# vr61-revC.net
KiCad netlist of a schematic drawn in EAGLE
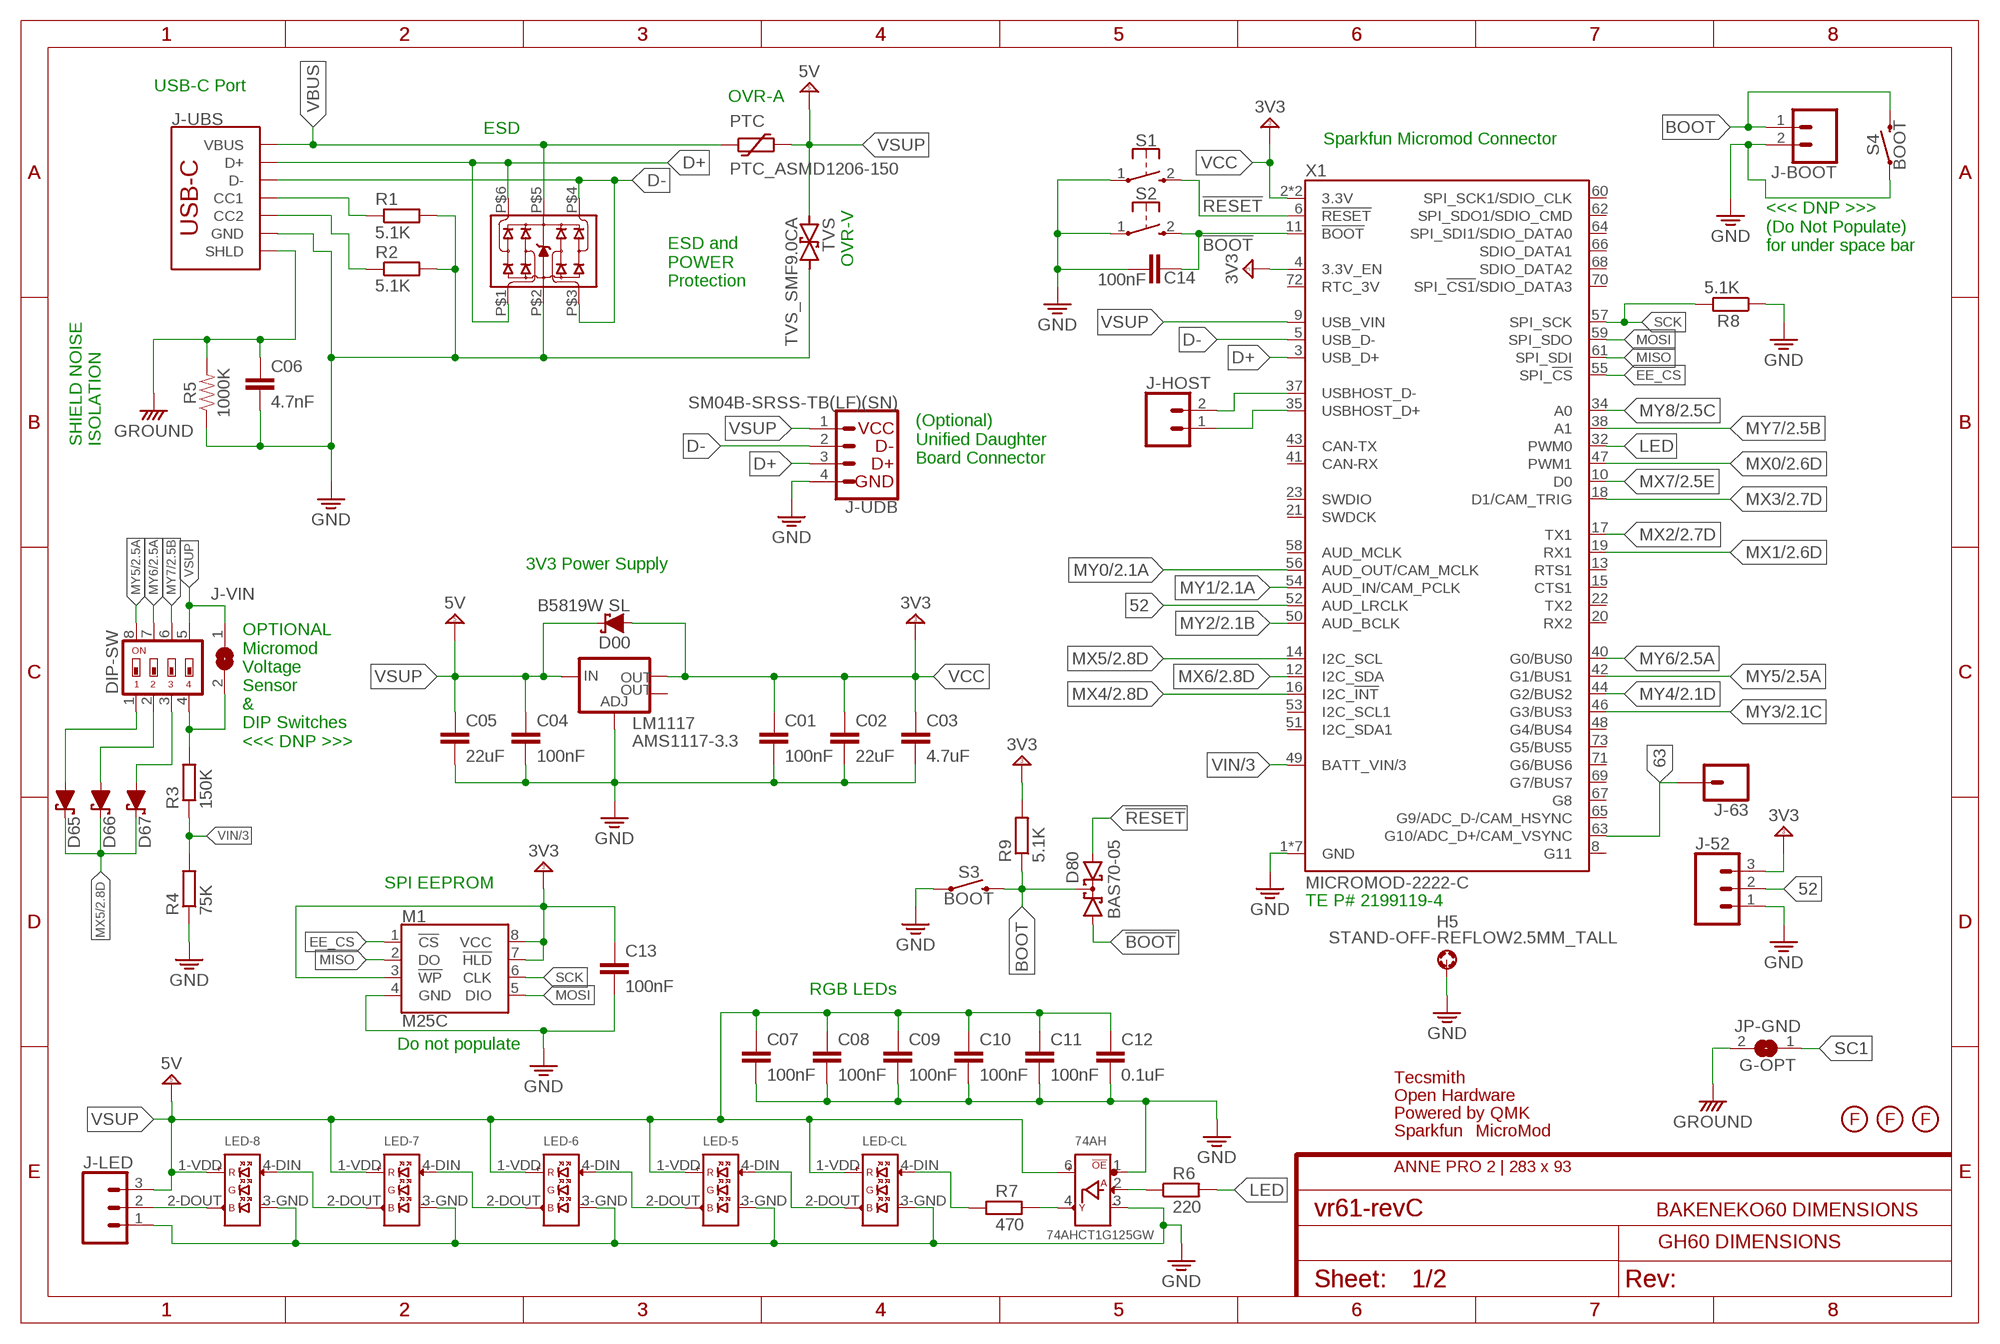
[diagram p0: schematic, sheet 1]
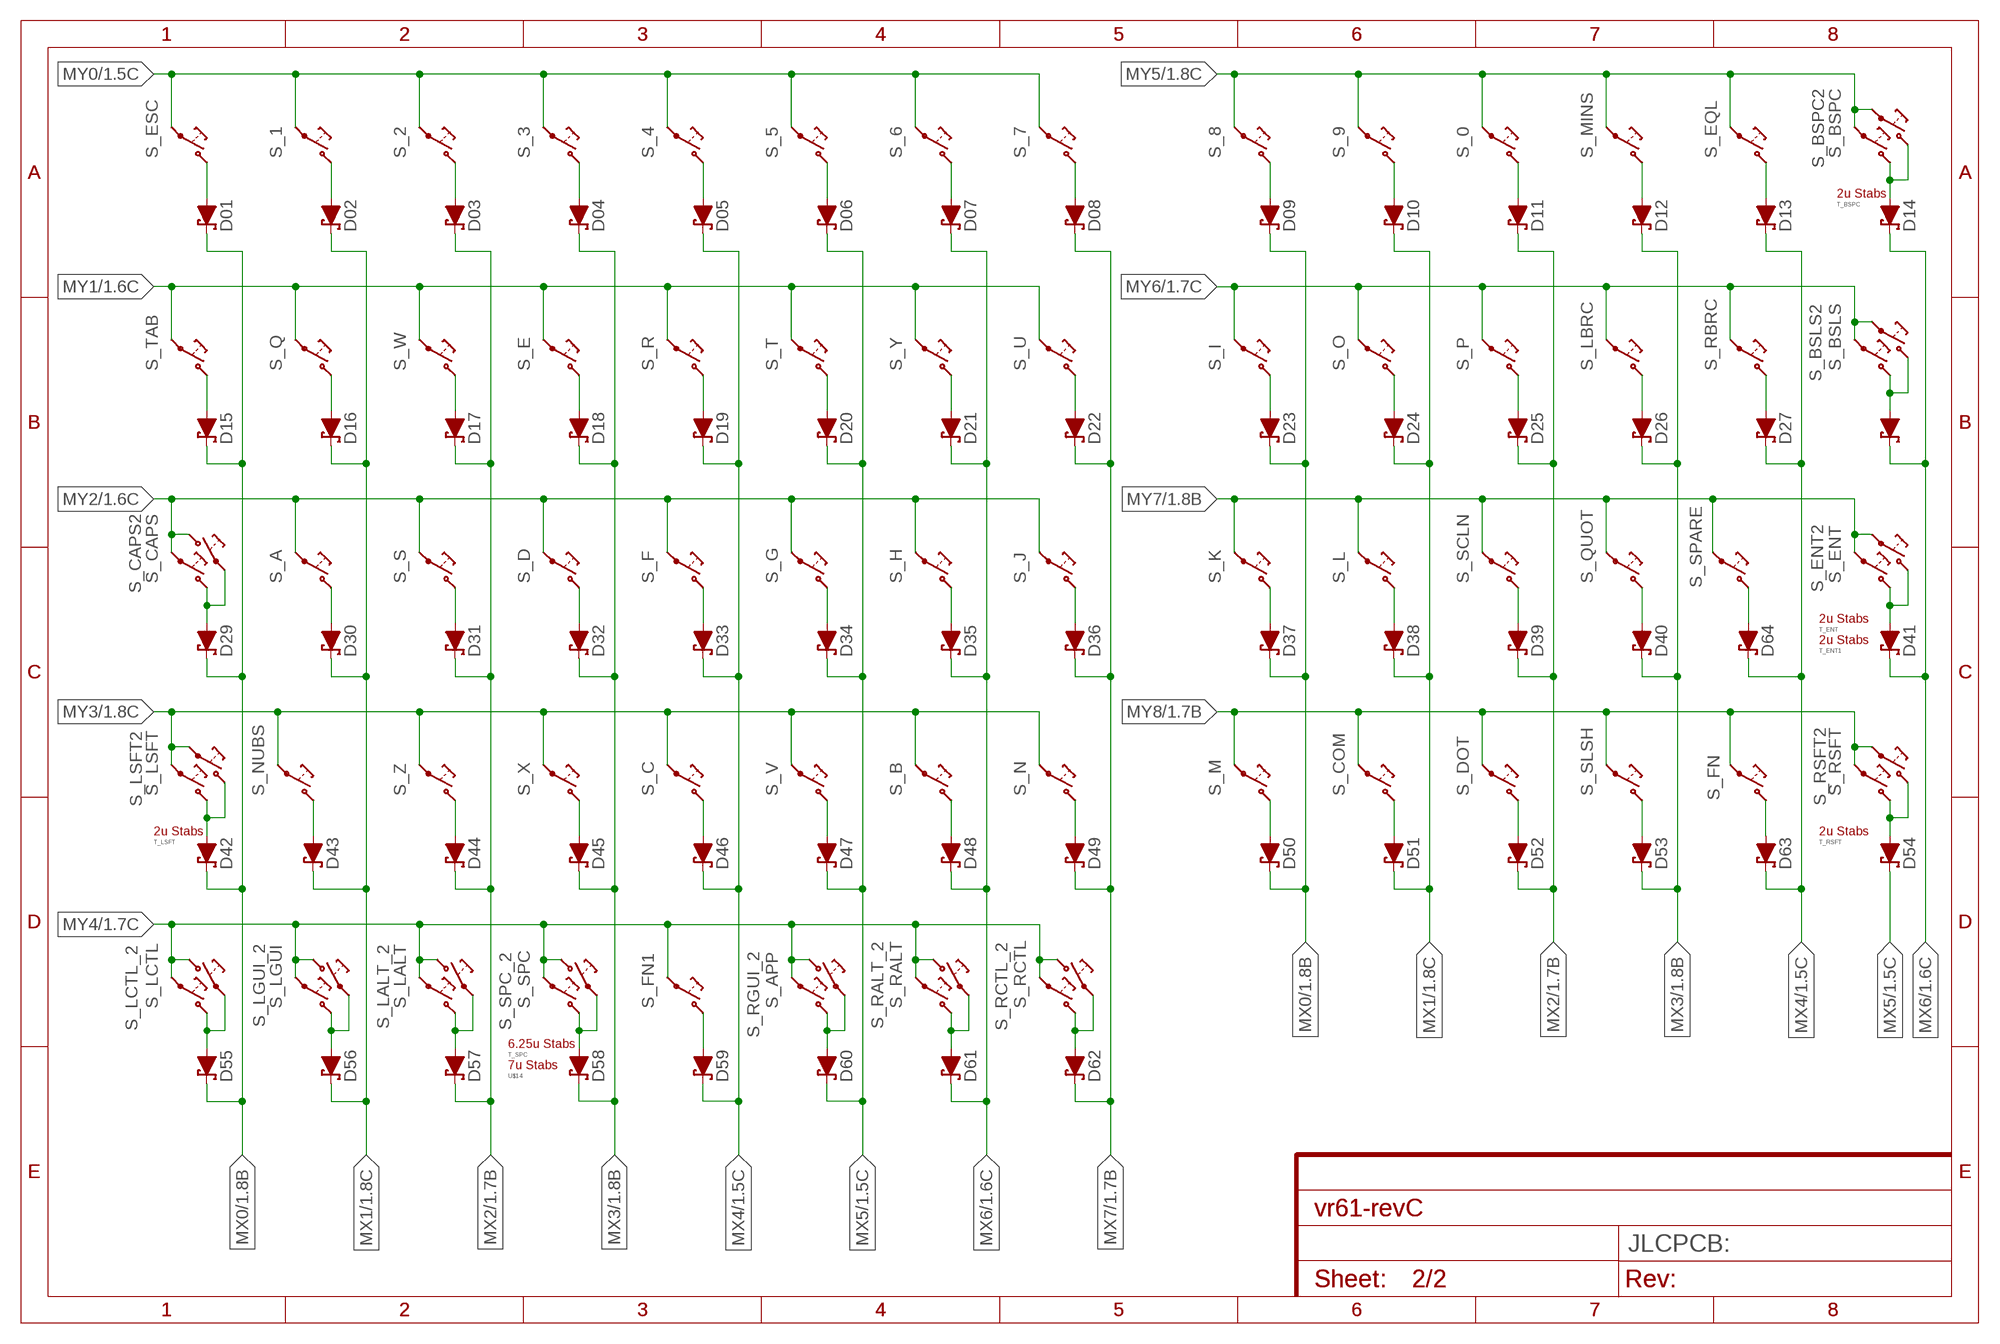
[diagram p1: schematic, sheet 2]

(export (version "E")
  (design (tool "Eeschema 10.0.6"))
  (components
    (comp (ref "D01")
      (value "1N5819WS")
      (footprint "eagle-import:SOD-123")
      (libsource (lib "eagle-import") (part "1N5819WS"))
    )
    (comp (ref "D02")
      (value "1N5819WS")
      (footprint "eagle-import:SOD-123")
      (libsource (lib "eagle-import") (part "1N5819WS"))
    )
    (comp (ref "D03")
      (value "1N5819WS")
      (footprint "eagle-import:SOD-123")
      (libsource (lib "eagle-import") (part "1N5819WS"))
    )
    (comp (ref "D04")
      (value "1N5819WS")
      (footprint "eagle-import:SOD-123")
      (libsource (lib "eagle-import") (part "1N5819WS"))
    )
    (comp (ref "D05")
      (value "1N5819WS")
      (footprint "eagle-import:SOD-123")
      (libsource (lib "eagle-import") (part "1N5819WS"))
    )
    (comp (ref "D06")
      (value "1N5819WS")
      (footprint "eagle-import:SOD-123")
      (libsource (lib "eagle-import") (part "1N5819WS"))
    )
    (comp (ref "D07")
      (value "1N5819WS")
      (footprint "eagle-import:SOD-123")
      (libsource (lib "eagle-import") (part "1N5819WS"))
    )
    (comp (ref "D08")
      (value "1N5819WS")
      (footprint "eagle-import:SOD-123")
      (libsource (lib "eagle-import") (part "1N5819WS"))
    )
    (comp (ref "D09")
      (value "1N5819WS")
      (footprint "eagle-import:SOD-123")
      (libsource (lib "eagle-import") (part "1N5819WS"))
    )
    (comp (ref "D10")
      (value "1N5819WS")
      (footprint "eagle-import:SOD-123")
      (libsource (lib "eagle-import") (part "1N5819WS"))
    )
    (comp (ref "D11")
      (value "1N5819WS")
      (footprint "eagle-import:SOD-123")
      (libsource (lib "eagle-import") (part "1N5819WS"))
    )
    (comp (ref "D12")
      (value "1N5819WS")
      (footprint "eagle-import:SOD-123")
      (libsource (lib "eagle-import") (part "1N5819WS"))
    )
    (comp (ref "D13")
      (value "1N5819WS")
      (footprint "eagle-import:SOD-123")
      (libsource (lib "eagle-import") (part "1N5819WS"))
    )
    (comp (ref "D14")
      (value "1N5819WS")
      (footprint "eagle-import:SOD-123")
      (libsource (lib "eagle-import") (part "1N5819WS"))
    )
    (comp (ref "D15")
      (value "1N5819WS")
      (footprint "eagle-import:SOD-123")
      (libsource (lib "eagle-import") (part "1N5819WS"))
    )
    (comp (ref "D16")
      (value "1N5819WS")
      (footprint "eagle-import:SOD-123")
      (libsource (lib "eagle-import") (part "1N5819WS"))
    )
    (comp (ref "D17")
      (value "1N5819WS")
      (footprint "eagle-import:SOD-123")
      (libsource (lib "eagle-import") (part "1N5819WS"))
    )
    (comp (ref "D18")
      (value "1N5819WS")
      (footprint "eagle-import:SOD-123")
      (libsource (lib "eagle-import") (part "1N5819WS"))
    )
    (comp (ref "D19")
      (value "1N5819WS")
      (footprint "eagle-import:SOD-123")
      (libsource (lib "eagle-import") (part "1N5819WS"))
    )
    (comp (ref "D20")
      (value "1N5819WS")
      (footprint "eagle-import:SOD-123")
      (libsource (lib "eagle-import") (part "1N5819WS"))
    )
    (comp (ref "D21")
      (value "1N5819WS")
      (footprint "eagle-import:SOD-123")
      (libsource (lib "eagle-import") (part "1N5819WS"))
    )
    (comp (ref "D22")
      (value "1N5819WS")
      (footprint "eagle-import:SOD-123")
      (libsource (lib "eagle-import") (part "1N5819WS"))
    )
    (comp (ref "D23")
      (value "1N5819WS")
      (footprint "eagle-import:SOD-123")
      (libsource (lib "eagle-import") (part "1N5819WS"))
    )
    (comp (ref "D24")
      (value "1N5819WS")
      (footprint "eagle-import:SOD-123")
      (libsource (lib "eagle-import") (part "1N5819WS"))
    )
    (comp (ref "D25")
      (value "1N5819WS")
      (footprint "eagle-import:SOD-123")
      (libsource (lib "eagle-import") (part "1N5819WS"))
    )
    (comp (ref "D26")
      (value "1N5819WS")
      (footprint "eagle-import:SOD-123")
      (libsource (lib "eagle-import") (part "1N5819WS"))
    )
    (comp (ref "D27")
      (value "1N5819WS")
      (footprint "eagle-import:SOD-123")
      (libsource (lib "eagle-import") (part "1N5819WS"))
    )
    (comp (ref "D28")
      (value "1N5819WS")
      (footprint "eagle-import:SOD-123")
      (libsource (lib "eagle-import") (part "1N5819WS"))
    )
    (comp (ref "D29")
      (value "1N5819WS")
      (footprint "eagle-import:SOD-123")
      (libsource (lib "eagle-import") (part "1N5819WS"))
    )
    (comp (ref "D30")
      (value "1N5819WS")
      (footprint "eagle-import:SOD-123")
      (libsource (lib "eagle-import") (part "1N5819WS"))
    )
    (comp (ref "D31")
      (value "1N5819WS")
      (footprint "eagle-import:SOD-123")
      (libsource (lib "eagle-import") (part "1N5819WS"))
    )
    (comp (ref "D32")
      (value "1N5819WS")
      (footprint "eagle-import:SOD-123")
      (libsource (lib "eagle-import") (part "1N5819WS"))
    )
    (comp (ref "D33")
      (value "1N5819WS")
      (footprint "eagle-import:SOD-123")
      (libsource (lib "eagle-import") (part "1N5819WS"))
    )
    (comp (ref "D34")
      (value "1N5819WS")
      (footprint "eagle-import:SOD-123")
      (libsource (lib "eagle-import") (part "1N5819WS"))
    )
    (comp (ref "D35")
      (value "1N5819WS")
      (footprint "eagle-import:SOD-123")
      (libsource (lib "eagle-import") (part "1N5819WS"))
    )
    (comp (ref "D36")
      (value "1N5819WS")
      (footprint "eagle-import:SOD-123")
      (libsource (lib "eagle-import") (part "1N5819WS"))
    )
    (comp (ref "D37")
      (value "1N5819WS")
      (footprint "eagle-import:SOD-123")
      (libsource (lib "eagle-import") (part "1N5819WS"))
    )
    (comp (ref "D38")
      (value "1N5819WS")
      (footprint "eagle-import:SOD-123")
      (libsource (lib "eagle-import") (part "1N5819WS"))
    )
    (comp (ref "D39")
      (value "1N5819WS")
      (footprint "eagle-import:SOD-123")
      (libsource (lib "eagle-import") (part "1N5819WS"))
    )
    (comp (ref "D40")
      (value "1N5819WS")
      (footprint "eagle-import:SOD-123")
      (libsource (lib "eagle-import") (part "1N5819WS"))
    )
    (comp (ref "D41")
      (value "1N5819WS")
      (footprint "eagle-import:SOD-123")
      (libsource (lib "eagle-import") (part "1N5819WS"))
    )
    (comp (ref "D42")
      (value "1N5819WS")
      (footprint "eagle-import:SOD-123")
      (libsource (lib "eagle-import") (part "1N5819WS"))
    )
    (comp (ref "D43")
      (value "1N5819WS")
      (footprint "eagle-import:SOD-123")
      (libsource (lib "eagle-import") (part "1N5819WS"))
    )
    (comp (ref "D44")
      (value "1N5819WS")
      (footprint "eagle-import:SOD-123")
      (libsource (lib "eagle-import") (part "1N5819WS"))
    )
    (comp (ref "D45")
      (value "1N5819WS")
      (footprint "eagle-import:SOD-123")
      (libsource (lib "eagle-import") (part "1N5819WS"))
    )
    (comp (ref "D46")
      (value "1N5819WS")
      (footprint "eagle-import:SOD-123")
      (libsource (lib "eagle-import") (part "1N5819WS"))
    )
    (comp (ref "D47")
      (value "1N5819WS")
      (footprint "eagle-import:SOD-123")
      (libsource (lib "eagle-import") (part "1N5819WS"))
    )
    (comp (ref "D48")
      (value "1N5819WS")
      (footprint "eagle-import:SOD-123")
      (libsource (lib "eagle-import") (part "1N5819WS"))
    )
    (comp (ref "D49")
      (value "1N5819WS")
      (footprint "eagle-import:SOD-123")
      (libsource (lib "eagle-import") (part "1N5819WS"))
    )
    (comp (ref "D50")
      (value "1N5819WS")
      (footprint "eagle-import:SOD-123")
      (libsource (lib "eagle-import") (part "1N5819WS"))
    )
    (comp (ref "D51")
      (value "1N5819WS")
      (footprint "eagle-import:SOD-123")
      (libsource (lib "eagle-import") (part "1N5819WS"))
    )
    (comp (ref "D52")
      (value "1N5819WS")
      (footprint "eagle-import:SOD-123")
      (libsource (lib "eagle-import") (part "1N5819WS"))
    )
    (comp (ref "D53")
      (value "1N5819WS")
      (footprint "eagle-import:SOD-123")
      (libsource (lib "eagle-import") (part "1N5819WS"))
    )
    (comp (ref "D54")
      (value "1N5819WS")
      (footprint "eagle-import:SOD-123")
      (libsource (lib "eagle-import") (part "1N5819WS"))
    )
    (comp (ref "D55")
      (value "1N5819WS")
      (footprint "eagle-import:SOD-123")
      (libsource (lib "eagle-import") (part "1N5819WS"))
    )
    (comp (ref "D56")
      (value "1N5819WS")
      (footprint "eagle-import:SOD-123")
      (libsource (lib "eagle-import") (part "1N5819WS"))
    )
    (comp (ref "D57")
      (value "1N5819WS")
      (footprint "eagle-import:SOD-123")
      (libsource (lib "eagle-import") (part "1N5819WS"))
    )
    (comp (ref "D58")
      (value "1N5819WS")
      (footprint "eagle-import:SOD-123")
      (libsource (lib "eagle-import") (part "1N5819WS"))
    )
    (comp (ref "D59")
      (value "1N5819WS")
      (footprint "eagle-import:SOD-123")
      (libsource (lib "eagle-import") (part "1N5819WS"))
    )
    (comp (ref "D60")
      (value "1N5819WS")
      (footprint "eagle-import:SOD-123")
      (libsource (lib "eagle-import") (part "1N5819WS"))
    )
    (comp (ref "D61")
      (value "1N5819WS")
      (footprint "eagle-import:SOD-123")
      (libsource (lib "eagle-import") (part "1N5819WS"))
    )
    (comp (ref "D62")
      (value "1N5819WS")
      (footprint "eagle-import:SOD-123")
      (libsource (lib "eagle-import") (part "1N5819WS"))
    )
    (comp (ref "D63")
      (value "1N5819WS")
      (footprint "eagle-import:SOD-123")
      (libsource (lib "eagle-import") (part "1N5819WS"))
    )
    (comp (ref "D64")
      (value "1N5819WS")
      (footprint "eagle-import:SOD-123")
      (libsource (lib "eagle-import") (part "1N5819WS"))
    )
    (comp (ref "S_0")
      (value "MX-5-PIN-HOTSWAP-VIA")
      (footprint "eagle-import:MX-5-PIN-HOTSWAP-VIA")
      (libsource (lib "eagle-import") (part "MX-5-PIN-HOTSWAP-VIA"))
    )
    (comp (ref "S_1")
      (value "MX-5-PIN-HOTSWAP-VIA")
      (footprint "eagle-import:MX-5-PIN-HOTSWAP-VIA")
      (libsource (lib "eagle-import") (part "MX-5-PIN-HOTSWAP-VIA"))
    )
    (comp (ref "S_2")
      (value "MX-5-PIN-HOTSWAP-VIA")
      (footprint "eagle-import:MX-5-PIN-HOTSWAP-VIA")
      (libsource (lib "eagle-import") (part "MX-5-PIN-HOTSWAP-VIA"))
    )
    (comp (ref "S_3")
      (value "MX-5-PIN-HOTSWAP-VIA")
      (footprint "eagle-import:MX-5-PIN-HOTSWAP-VIA")
      (libsource (lib "eagle-import") (part "MX-5-PIN-HOTSWAP-VIA"))
    )
    (comp (ref "S_4")
      (value "MX-5-PIN-HOTSWAP-VIA")
      (footprint "eagle-import:MX-5-PIN-HOTSWAP-VIA")
      (libsource (lib "eagle-import") (part "MX-5-PIN-HOTSWAP-VIA"))
    )
    (comp (ref "S_5")
      (value "MX-5-PIN-HOTSWAP-VIA")
      (footprint "eagle-import:MX-5-PIN-HOTSWAP-VIA")
      (libsource (lib "eagle-import") (part "MX-5-PIN-HOTSWAP-VIA"))
    )
    (comp (ref "S_6")
      (value "MX-5-PIN-HOTSWAP-VIA")
      (footprint "eagle-import:MX-5-PIN-HOTSWAP-VIA")
      (libsource (lib "eagle-import") (part "MX-5-PIN-HOTSWAP-VIA"))
    )
    (comp (ref "S_7")
      (value "MX-5-PIN-HOTSWAP-VIA")
      (footprint "eagle-import:MX-5-PIN-HOTSWAP-VIA")
      (libsource (lib "eagle-import") (part "MX-5-PIN-HOTSWAP-VIA"))
    )
    (comp (ref "S_8")
      (value "MX-5-PIN-HOTSWAP-VIA")
      (footprint "eagle-import:MX-5-PIN-HOTSWAP-VIA")
      (libsource (lib "eagle-import") (part "MX-5-PIN-HOTSWAP-VIA"))
    )
    (comp (ref "S_9")
      (value "MX-5-PIN-HOTSWAP-VIA")
      (footprint "eagle-import:MX-5-PIN-HOTSWAP-VIA")
      (libsource (lib "eagle-import") (part "MX-5-PIN-HOTSWAP-VIA"))
    )
    (comp (ref "S_A")
      (value "MX-5-PIN-HOTSWAP-VIA")
      (footprint "eagle-import:MX-5-PIN-HOTSWAP-VIA")
      (libsource (lib "eagle-import") (part "MX-5-PIN-HOTSWAP-VIA"))
    )
    (comp (ref "S_APP")
      (value "MX-5-PIN-HOTSWAP-VIA")
      (footprint "eagle-import:MX-5-PIN-HOTSWAP-VIA")
      (libsource (lib "eagle-import") (part "MX-5-PIN-HOTSWAP-VIA"))
    )
    (comp (ref "S_B")
      (value "MX-5-PIN-HOTSWAP-VIA")
      (footprint "eagle-import:MX-5-PIN-HOTSWAP-VIA")
      (libsource (lib "eagle-import") (part "MX-5-PIN-HOTSWAP-VIA"))
    )
    (comp (ref "S_BSLS")
      (value "MX-5-PIN-HOTSWAP-VIA")
      (footprint "eagle-import:MX-5-PIN-HOTSWAP-VIA")
      (libsource (lib "eagle-import") (part "MX-5-PIN-HOTSWAP-VIA"))
    )
    (comp (ref "S_BSLS2")
      (value "MX-5-PIN-HOTSWAP-VIANO-SILK")
      (footprint "eagle-import:MX-5-PIN-HOTSWAP-VIA-NS")
      (libsource (lib "eagle-import") (part "MX-5-PIN-HOTSWAP-VIANO-SILK"))
    )
    (comp (ref "S_BSPC")
      (value "MX-5-PIN-HOTSWAP-VIA")
      (footprint "eagle-import:MX-5-PIN-HOTSWAP-VIA")
      (libsource (lib "eagle-import") (part "MX-5-PIN-HOTSWAP-VIA"))
    )
    (comp (ref "S_BSPC2")
      (value "MX-5-PIN-HOTSWAP-VIANO-SILK")
      (footprint "eagle-import:MX-5-PIN-HOTSWAP-VIA-NS")
      (libsource (lib "eagle-import") (part "MX-5-PIN-HOTSWAP-VIANO-SILK"))
    )
    (comp (ref "S_C")
      (value "MX-5-PIN-HOTSWAP-VIA")
      (footprint "eagle-import:MX-5-PIN-HOTSWAP-VIA")
      (libsource (lib "eagle-import") (part "MX-5-PIN-HOTSWAP-VIA"))
    )
    (comp (ref "S_CAPS")
      (value "MX-5-PIN-HOTSWAP-VIA")
      (footprint "eagle-import:MX-5-PIN-HOTSWAP-VIA")
      (libsource (lib "eagle-import") (part "MX-5-PIN-HOTSWAP-VIA"))
    )
    (comp (ref "S_CAPS2")
      (value "MX-5-PIN-MILMAX-3305-XNO-SILK")
      (footprint "eagle-import:MX-5-PIN-MILMAX-3305-X-NS")
      (libsource (lib "eagle-import") (part "MX-5-PIN-MILMAX-3305-XNO-SILK"))
    )
    (comp (ref "S_COM")
      (value "MX-5-PIN-HOTSWAP-VIA")
      (footprint "eagle-import:MX-5-PIN-HOTSWAP-VIA")
      (libsource (lib "eagle-import") (part "MX-5-PIN-HOTSWAP-VIA"))
    )
    (comp (ref "S_D")
      (value "MX-5-PIN-HOTSWAP-VIA")
      (footprint "eagle-import:MX-5-PIN-HOTSWAP-VIA")
      (libsource (lib "eagle-import") (part "MX-5-PIN-HOTSWAP-VIA"))
    )
    (comp (ref "S_DOT")
      (value "MX-5-PIN-HOTSWAP-VIA")
      (footprint "eagle-import:MX-5-PIN-HOTSWAP-VIA")
      (libsource (lib "eagle-import") (part "MX-5-PIN-HOTSWAP-VIA"))
    )
    (comp (ref "S_E")
      (value "MX-5-PIN-HOTSWAP-VIA")
      (footprint "eagle-import:MX-5-PIN-HOTSWAP-VIA")
      (libsource (lib "eagle-import") (part "MX-5-PIN-HOTSWAP-VIA"))
    )
    (comp (ref "S_ENT")
      (value "MX-5-PIN-HOTSWAP-VIA")
      (footprint "eagle-import:MX-5-PIN-HOTSWAP-VIA")
      (libsource (lib "eagle-import") (part "MX-5-PIN-HOTSWAP-VIA"))
    )
    (comp (ref "S_ENT2")
      (value "MX-5-PIN-HOTSWAP-VIANO-SILK")
      (footprint "eagle-import:MX-5-PIN-HOTSWAP-VIA-NS")
      (libsource (lib "eagle-import") (part "MX-5-PIN-HOTSWAP-VIANO-SILK"))
    )
    (comp (ref "S_EQL")
      (value "MX-5-PIN-HOTSWAP-VIA")
      (footprint "eagle-import:MX-5-PIN-HOTSWAP-VIA")
      (libsource (lib "eagle-import") (part "MX-5-PIN-HOTSWAP-VIA"))
    )
    (comp (ref "S_ESC")
      (value "MX-5-PIN-HOTSWAP-VIA")
      (footprint "eagle-import:MX-5-PIN-HOTSWAP-VIA")
      (libsource (lib "eagle-import") (part "MX-5-PIN-HOTSWAP-VIA"))
    )
    (comp (ref "S_F")
      (value "MX-5-PIN-HOTSWAP-VIA")
      (footprint "eagle-import:MX-5-PIN-HOTSWAP-VIA")
      (libsource (lib "eagle-import") (part "MX-5-PIN-HOTSWAP-VIA"))
    )
    (comp (ref "S_FN")
      (value "MX-5-PIN-HOTSWAP-VIANO-SILK")
      (footprint "eagle-import:MX-5-PIN-HOTSWAP-VIA-NS")
      (libsource (lib "eagle-import") (part "MX-5-PIN-HOTSWAP-VIANO-SILK"))
    )
    (comp (ref "S_FN1")
      (value "MX-5-PIN-HOTSWAP-VIA")
      (footprint "eagle-import:MX-5-PIN-HOTSWAP-VIA")
      (libsource (lib "eagle-import") (part "MX-5-PIN-HOTSWAP-VIA"))
    )
    (comp (ref "S_G")
      (value "MX-5-PIN-HOTSWAP-VIA")
      (footprint "eagle-import:MX-5-PIN-HOTSWAP-VIA")
      (libsource (lib "eagle-import") (part "MX-5-PIN-HOTSWAP-VIA"))
    )
    (comp (ref "S_H")
      (value "MX-5-PIN-HOTSWAP-VIA")
      (footprint "eagle-import:MX-5-PIN-HOTSWAP-VIA")
      (libsource (lib "eagle-import") (part "MX-5-PIN-HOTSWAP-VIA"))
    )
    (comp (ref "S_I")
      (value "MX-5-PIN-HOTSWAP-VIA")
      (footprint "eagle-import:MX-5-PIN-HOTSWAP-VIA")
      (libsource (lib "eagle-import") (part "MX-5-PIN-HOTSWAP-VIA"))
    )
    (comp (ref "S_J")
      (value "MX-5-PIN-HOTSWAP-VIA")
      (footprint "eagle-import:MX-5-PIN-HOTSWAP-VIA")
      (libsource (lib "eagle-import") (part "MX-5-PIN-HOTSWAP-VIA"))
    )
    (comp (ref "S_K")
      (value "MX-5-PIN-HOTSWAP-VIA")
      (footprint "eagle-import:MX-5-PIN-HOTSWAP-VIA")
      (libsource (lib "eagle-import") (part "MX-5-PIN-HOTSWAP-VIA"))
    )
    (comp (ref "S_L")
      (value "MX-5-PIN-HOTSWAP-VIA")
      (footprint "eagle-import:MX-5-PIN-HOTSWAP-VIA")
      (libsource (lib "eagle-import") (part "MX-5-PIN-HOTSWAP-VIA"))
    )
    (comp (ref "S_LALT")
      (value "MX-5-PIN-HOTSWAP-VIA")
      (footprint "eagle-import:MX-5-PIN-HOTSWAP-VIA")
      (libsource (lib "eagle-import") (part "MX-5-PIN-HOTSWAP-VIA"))
    )
    (comp (ref "S_LALT_2")
      (value "MX-5-PIN-HOTSWAP-VIANO-SILK")
      (footprint "eagle-import:MX-5-PIN-HOTSWAP-VIA-NS")
      (libsource (lib "eagle-import") (part "MX-5-PIN-HOTSWAP-VIANO-SILK"))
    )
    (comp (ref "S_LBRC")
      (value "MX-5-PIN-HOTSWAP-VIA")
      (footprint "eagle-import:MX-5-PIN-HOTSWAP-VIA")
      (libsource (lib "eagle-import") (part "MX-5-PIN-HOTSWAP-VIA"))
    )
    (comp (ref "S_LCTL")
      (value "MX-5-PIN-HOTSWAP-VIA")
      (footprint "eagle-import:MX-5-PIN-HOTSWAP-VIA")
      (libsource (lib "eagle-import") (part "MX-5-PIN-HOTSWAP-VIA"))
    )
    (comp (ref "S_LCTL_2")
      (value "MX-5-PIN-HOTSWAP-VIANO-SILK")
      (footprint "eagle-import:MX-5-PIN-HOTSWAP-VIA-NS")
      (libsource (lib "eagle-import") (part "MX-5-PIN-HOTSWAP-VIANO-SILK"))
    )
    (comp (ref "S_LGUI")
      (value "MX-5-PIN-HOTSWAP-VIA")
      (footprint "eagle-import:MX-5-PIN-HOTSWAP-VIA")
      (libsource (lib "eagle-import") (part "MX-5-PIN-HOTSWAP-VIA"))
    )
    (comp (ref "S_LGUI_2")
      (value "MX-5-PIN-HOTSWAP-VIANO-SILK")
      (footprint "eagle-import:MX-5-PIN-HOTSWAP-VIA-NS")
      (libsource (lib "eagle-import") (part "MX-5-PIN-HOTSWAP-VIANO-SILK"))
    )
    (comp (ref "S_LSFT")
      (value "MX-5-PIN-HOTSWAP-VIA")
      (footprint "eagle-import:MX-5-PIN-HOTSWAP-VIA")
      (libsource (lib "eagle-import") (part "MX-5-PIN-HOTSWAP-VIA"))
    )
    (comp (ref "S_LSFT2")
      (value "MX-5-PIN-HOTSWAP-VIANO-SILK")
      (footprint "eagle-import:MX-5-PIN-HOTSWAP-VIA-NS")
      (libsource (lib "eagle-import") (part "MX-5-PIN-HOTSWAP-VIANO-SILK"))
    )
    (comp (ref "S_M")
      (value "MX-5-PIN-HOTSWAP-VIA")
      (footprint "eagle-import:MX-5-PIN-HOTSWAP-VIA")
      (libsource (lib "eagle-import") (part "MX-5-PIN-HOTSWAP-VIA"))
    )
    (comp (ref "S_MINS")
      (value "MX-5-PIN-HOTSWAP-VIA")
      (footprint "eagle-import:MX-5-PIN-HOTSWAP-VIA")
      (libsource (lib "eagle-import") (part "MX-5-PIN-HOTSWAP-VIA"))
    )
    (comp (ref "S_N")
      (value "MX-5-PIN-HOTSWAP-VIA")
      (footprint "eagle-import:MX-5-PIN-HOTSWAP-VIA")
      (libsource (lib "eagle-import") (part "MX-5-PIN-HOTSWAP-VIA"))
    )
    (comp (ref "S_NUBS")
      (value "MX-5-PIN-HOTSWAP-VIANO-SILK")
      (footprint "eagle-import:MX-5-PIN-HOTSWAP-VIA-NS")
      (libsource (lib "eagle-import") (part "MX-5-PIN-HOTSWAP-VIANO-SILK"))
    )
    (comp (ref "S_O")
      (value "MX-5-PIN-HOTSWAP-VIA")
      (footprint "eagle-import:MX-5-PIN-HOTSWAP-VIA")
      (libsource (lib "eagle-import") (part "MX-5-PIN-HOTSWAP-VIA"))
    )
    (comp (ref "S_P")
      (value "MX-5-PIN-HOTSWAP-VIA")
      (footprint "eagle-import:MX-5-PIN-HOTSWAP-VIA")
      (libsource (lib "eagle-import") (part "MX-5-PIN-HOTSWAP-VIA"))
    )
    (comp (ref "S_Q")
      (value "MX-5-PIN-HOTSWAP-VIA")
      (footprint "eagle-import:MX-5-PIN-HOTSWAP-VIA")
      (libsource (lib "eagle-import") (part "MX-5-PIN-HOTSWAP-VIA"))
    )
    (comp (ref "S_QUOT")
      (value "MX-5-PIN-HOTSWAP-VIA")
      (footprint "eagle-import:MX-5-PIN-HOTSWAP-VIA")
      (libsource (lib "eagle-import") (part "MX-5-PIN-HOTSWAP-VIA"))
    )
    (comp (ref "S_R")
      (value "MX-5-PIN-HOTSWAP-VIA")
      (footprint "eagle-import:MX-5-PIN-HOTSWAP-VIA")
      (libsource (lib "eagle-import") (part "MX-5-PIN-HOTSWAP-VIA"))
    )
    (comp (ref "S_RALT")
      (value "MX-5-PIN-HOTSWAP-VIA")
      (footprint "eagle-import:MX-5-PIN-HOTSWAP-VIA")
      (libsource (lib "eagle-import") (part "MX-5-PIN-HOTSWAP-VIA"))
    )
    (comp (ref "S_RALT_2")
      (value "MX-5-PIN-HOTSWAP-VIANO-SILK")
      (footprint "eagle-import:MX-5-PIN-HOTSWAP-VIA-NS")
      (libsource (lib "eagle-import") (part "MX-5-PIN-HOTSWAP-VIANO-SILK"))
    )
    (comp (ref "S_RBRC")
      (value "MX-5-PIN-HOTSWAP-VIA")
      (footprint "eagle-import:MX-5-PIN-HOTSWAP-VIA")
      (libsource (lib "eagle-import") (part "MX-5-PIN-HOTSWAP-VIA"))
    )
    (comp (ref "S_RCTL")
      (value "MX-5-PIN-HOTSWAP-VIA")
      (footprint "eagle-import:MX-5-PIN-HOTSWAP-VIA")
      (libsource (lib "eagle-import") (part "MX-5-PIN-HOTSWAP-VIA"))
    )
    (comp (ref "S_RCTL_2")
      (value "MX-5-PIN-HOTSWAP-VIANO-SILK")
      (footprint "eagle-import:MX-5-PIN-HOTSWAP-VIA-NS")
      (libsource (lib "eagle-import") (part "MX-5-PIN-HOTSWAP-VIANO-SILK"))
    )
    (comp (ref "S_RGUI_2")
      (value "MX-5-PIN-HOTSWAP-VIANO-SILK")
      (footprint "eagle-import:MX-5-PIN-HOTSWAP-VIA-NS")
      (libsource (lib "eagle-import") (part "MX-5-PIN-HOTSWAP-VIANO-SILK"))
    )
    (comp (ref "S_RSFT")
      (value "MX-5-PIN-HOTSWAP-VIA")
      (footprint "eagle-import:MX-5-PIN-HOTSWAP-VIA")
      (libsource (lib "eagle-import") (part "MX-5-PIN-HOTSWAP-VIA"))
    )
    (comp (ref "S_RSFT2")
      (value "MX-5-PIN-HOTSWAP-VIANO-SILK")
      (footprint "eagle-import:MX-5-PIN-HOTSWAP-VIA-NS")
      (libsource (lib "eagle-import") (part "MX-5-PIN-HOTSWAP-VIANO-SILK"))
    )
    (comp (ref "S_S")
      (value "MX-5-PIN-HOTSWAP-VIA")
      (footprint "eagle-import:MX-5-PIN-HOTSWAP-VIA")
      (libsource (lib "eagle-import") (part "MX-5-PIN-HOTSWAP-VIA"))
    )
    (comp (ref "S_SCLN")
      (value "MX-5-PIN-HOTSWAP-VIA")
      (footprint "eagle-import:MX-5-PIN-HOTSWAP-VIA")
      (libsource (lib "eagle-import") (part "MX-5-PIN-HOTSWAP-VIA"))
    )
    (comp (ref "S_SLSH")
      (value "MX-5-PIN-HOTSWAP-VIA")
      (footprint "eagle-import:MX-5-PIN-HOTSWAP-VIA")
      (libsource (lib "eagle-import") (part "MX-5-PIN-HOTSWAP-VIA"))
    )
    (comp (ref "S_SPARE")
      (value "MX-5-PIN-HOTSWAP-VIANO-SILK")
      (footprint "eagle-import:MX-5-PIN-HOTSWAP-VIA-NS")
      (libsource (lib "eagle-import") (part "MX-5-PIN-HOTSWAP-VIANO-SILK"))
    )
    (comp (ref "S_SPC")
      (value "MX-5-PIN-HOTSWAP-VIA")
      (footprint "eagle-import:MX-5-PIN-HOTSWAP-VIA")
      (libsource (lib "eagle-import") (part "MX-5-PIN-HOTSWAP-VIA"))
    )
    (comp (ref "S_SPC_2")
      (value "MX-5-PIN-HOTSWAP-VIANO-SILK")
      (footprint "eagle-import:MX-5-PIN-HOTSWAP-VIA-NS")
      (libsource (lib "eagle-import") (part "MX-5-PIN-HOTSWAP-VIANO-SILK"))
    )
    (comp (ref "S_T")
      (value "MX-5-PIN-HOTSWAP-VIA")
      (footprint "eagle-import:MX-5-PIN-HOTSWAP-VIA")
      (libsource (lib "eagle-import") (part "MX-5-PIN-HOTSWAP-VIA"))
    )
    (comp (ref "S_TAB")
      (value "MX-5-PIN-HOTSWAP-VIA")
      (footprint "eagle-import:MX-5-PIN-HOTSWAP-VIA")
      (libsource (lib "eagle-import") (part "MX-5-PIN-HOTSWAP-VIA"))
    )
    (comp (ref "S_U")
      (value "MX-5-PIN-HOTSWAP-VIA")
      (footprint "eagle-import:MX-5-PIN-HOTSWAP-VIA")
      (libsource (lib "eagle-import") (part "MX-5-PIN-HOTSWAP-VIA"))
    )
    (comp (ref "S_V")
      (value "MX-5-PIN-HOTSWAP-VIA")
      (footprint "eagle-import:MX-5-PIN-HOTSWAP-VIA")
      (libsource (lib "eagle-import") (part "MX-5-PIN-HOTSWAP-VIA"))
    )
    (comp (ref "S_W")
      (value "MX-5-PIN-HOTSWAP-VIA")
      (footprint "eagle-import:MX-5-PIN-HOTSWAP-VIA")
      (libsource (lib "eagle-import") (part "MX-5-PIN-HOTSWAP-VIA"))
    )
    (comp (ref "S_X")
      (value "MX-5-PIN-HOTSWAP-VIA")
      (footprint "eagle-import:MX-5-PIN-HOTSWAP-VIA")
      (libsource (lib "eagle-import") (part "MX-5-PIN-HOTSWAP-VIA"))
    )
    (comp (ref "S_Y")
      (value "MX-5-PIN-HOTSWAP-VIA")
      (footprint "eagle-import:MX-5-PIN-HOTSWAP-VIA")
      (libsource (lib "eagle-import") (part "MX-5-PIN-HOTSWAP-VIA"))
    )
    (comp (ref "S_Z")
      (value "MX-5-PIN-HOTSWAP-VIA")
      (footprint "eagle-import:MX-5-PIN-HOTSWAP-VIA")
      (libsource (lib "eagle-import") (part "MX-5-PIN-HOTSWAP-VIA"))
    )
    (comp (ref "T_BSPC")
      (value "MX-STABS-200U")
      (footprint "eagle-import:MX-STABS-200U")
      (libsource (lib "eagle-import") (part "MX-STABS-200U"))
    )
    (comp (ref "T_ENT")
      (value "MX-STABS-200U")
      (footprint "eagle-import:MX-STABS-200U")
      (libsource (lib "eagle-import") (part "MX-STABS-200U"))
    )
    (comp (ref "T_ENT1")
      (value "MX-STABS-200U")
      (footprint "eagle-import:MX-STABS-200U")
      (libsource (lib "eagle-import") (part "MX-STABS-200U"))
    )
    (comp (ref "T_LSFT")
      (value "MX-STABS-200U")
      (footprint "eagle-import:MX-STABS-200U")
      (libsource (lib "eagle-import") (part "MX-STABS-200U"))
    )
    (comp (ref "T_RSFT")
      (value "MX-STABS-200U")
      (footprint "eagle-import:MX-STABS-200U")
      (libsource (lib "eagle-import") (part "MX-STABS-200U"))
    )
    (comp (ref "T_SPC")
      (value "MX-STABS-625U")
      (footprint "eagle-import:MX-STABS-625U")
      (libsource (lib "eagle-import") (part "MX-STABS-625U"))
    )
    (comp (ref "U$14")
      (value "MX-STABS-700U")
      (footprint "eagle-import:MX-STABS-700U")
      (libsource (lib "eagle-import") (part "MX-STABS-700U"))
    )
    (comp (ref "U$26")
      (value "?")
      (footprint "eagle-import:JLC_ORDER_NUMBER_QR_5X5")
      (libsource (lib "eagle-import") (part "JLC_ORDER_NUMBER_QRQR_5X5"))
    )
    (comp (ref "74AH")
      (value "74AHCT1G125GW")
      (footprint "eagle-import:SC-88A__TSSOP5__SOT353-1")
      (libsource (lib "eagle-import") (part "74AHCT1G125GW"))
    )
    (comp (ref "C01")
      (value "100nF")
      (footprint "eagle-import:0603")
      (libsource (lib "eagle-import") (part "0.1UF-0603-25V-5%"))
    )
    (comp (ref "C02")
      (value "22uF")
      (footprint "eagle-import:0603")
      (libsource (lib "eagle-import") (part "0.22UF-0603-25V-10%"))
    )
    (comp (ref "C03")
      (value "4.7uF")
      (footprint "eagle-import:0603")
      (libsource (lib "eagle-import") (part "1.0NF/1000PF-0603-50V-10%"))
    )
    (comp (ref "C04")
      (value "100nF")
      (footprint "eagle-import:0603")
      (libsource (lib "eagle-import") (part "0.1UF-0603-25V-5%"))
    )
    (comp (ref "C05")
      (value "22uF")
      (footprint "eagle-import:0603")
      (libsource (lib "eagle-import") (part "0.22UF-0603-25V-10%"))
    )
    (comp (ref "C06")
      (value "4.7nF")
      (footprint "eagle-import:0603")
      (libsource (lib "eagle-import") (part "0.1UF-0603-25V-5%"))
    )
    (comp (ref "C07")
      (value "100nF")
      (footprint "eagle-import:C0603")
      (libsource (lib "eagle-import") (part "C-EUC0603"))
    )
    (comp (ref "C08")
      (value "100nF")
      (footprint "eagle-import:C0603")
      (libsource (lib "eagle-import") (part "C-EUC0603"))
    )
    (comp (ref "C09")
      (value "100nF")
      (footprint "eagle-import:C0603")
      (libsource (lib "eagle-import") (part "C-EUC0603"))
    )
    (comp (ref "C10")
      (value "100nF")
      (footprint "eagle-import:C0603")
      (libsource (lib "eagle-import") (part "C-EUC0603"))
    )
    (comp (ref "C11")
      (value "100nF")
      (footprint "eagle-import:C0603")
      (libsource (lib "eagle-import") (part "C-EUC0603"))
    )
    (comp (ref "C12")
      (value "0.1uF")
      (footprint "eagle-import:C0603")
      (libsource (lib "eagle-import") (part "C-EUC0603"))
    )
    (comp (ref "C13")
      (value "100nF")
      (footprint "eagle-import:C0603")
      (libsource (lib "eagle-import") (part "C-EUC0603"))
    )
    (comp (ref "C14")
      (value "100nF")
      (footprint "eagle-import:C0603")
      (libsource (lib "eagle-import") (part "C-EUC0603"))
    )
    (comp (ref "D00")
      (value "B5819W SL")
      (footprint "eagle-import:SOD-123")
      (libsource (lib "eagle-import") (part "1N5819WS"))
    )
    (comp (ref "D65")
      (value "1N5819WS")
      (footprint "eagle-import:SOD-123")
      (libsource (lib "eagle-import") (part "1N5819WS"))
    )
    (comp (ref "D66")
      (value "1N5819WS")
      (footprint "eagle-import:SOD-123")
      (libsource (lib "eagle-import") (part "1N5819WS"))
    )
    (comp (ref "D67")
      (value "1N5819WS")
      (footprint "eagle-import:SOD-123")
      (libsource (lib "eagle-import") (part "1N5819WS"))
    )
    (comp (ref "D80")
      (value "BAS70-05")
      (footprint "eagle-import:SOT23")
      (libsource (lib "eagle-import") (part "BAS70-05"))
    )
    (comp (ref "DIP-SW")
      (value "DIP004")
      (footprint "eagle-import:DIP-1.27-004")
      (libsource (lib "eagle-import") (part "DIP004"))
    )
    (comp (ref "ESD")
      (value "ESD_SRV05-4")
      (footprint "eagle-import:SOT-23-6L")
      (libsource (lib "eagle-import") (part "ESD_SRV05-4"))
    )
    (comp (ref "FP_AP2")
      (value "FOOTPRINT-AP2")
      (footprint "eagle-import:FOOTPRINT-AP2")
      (libsource (lib "eagle-import") (part "FOOTPRINT-AP2"))
    )
    (comp (ref "H5")
      (value "STAND-OFF-REFLOW2.5MM_TALL")
      (footprint "eagle-import:STAND-OFF-REFLOW-M2.5")
      (libsource (lib "eagle-import") (part "STAND-OFF-REFLOW2.5MM_TALL"))
    )
    (comp (ref "J-52")
      (value "CONN_03")
      (footprint "eagle-import:1X03")
      (libsource (lib "eagle-import") (part "CONN_03"))
    )
    (comp (ref "J-63")
      (value "CONN_01")
      (footprint "eagle-import:1X01")
      (libsource (lib "eagle-import") (part "CONN_01"))
    )
    (comp (ref "J-BOOT")
      (value "CONN_02")
      (footprint "eagle-import:1X02")
      (libsource (lib "eagle-import") (part "CONN_02"))
    )
    (comp (ref "J-HOST")
      (value "CONN_02")
      (footprint "eagle-import:1X02")
      (libsource (lib "eagle-import") (part "CONN_02"))
    )
    (comp (ref "J-LED")
      (value "CONN_03")
      (footprint "eagle-import:1X03")
      (libsource (lib "eagle-import") (part "CONN_03"))
    )
    (comp (ref "J-UBS")
      (value "USB_C_2-LAYER")
      (footprint "eagle-import:USB-C-16P")
      (libsource (lib "eagle-import") (part "USB_C_2-LAYER"))
    )
    (comp (ref "J-UDB")
      (value "SM04B-SRSS-TB(LF)(SN)")
      (footprint "eagle-import:1X04_1MM_RA")
      (libsource (lib "eagle-import") (part "C3_UNIFIEDJS-1MM"))
    )
    (comp (ref "J-VIN")
      (value "JUMPER-1X2")
      (footprint "eagle-import:SOLDERJUMPER_ARROW_NOPASTE")
      (libsource (lib "eagle-import") (part "JUMPER-1X2"))
    )
    (comp (ref "JP-GND")
      (value "G-OPT")
      (footprint "eagle-import:SOLDERJUMPER_ARROW_NOPASTE")
      (libsource (lib "eagle-import") (part "JUMPER-1X2"))
    )
    (comp (ref "LED-5")
      (value "SK6812-E-REVERSE")
      (footprint "eagle-import:SK6812-E-MILL")
      (libsource (lib "eagle-import") (part "SK6812-E-REVERSE"))
    )
    (comp (ref "LED-6")
      (value "SK6812-E-REVERSE")
      (footprint "eagle-import:SK6812-E-MILL")
      (libsource (lib "eagle-import") (part "SK6812-E-REVERSE"))
    )
    (comp (ref "LED-7")
      (value "SK6812-E-REVERSE")
      (footprint "eagle-import:SK6812-E-MILL")
      (libsource (lib "eagle-import") (part "SK6812-E-REVERSE"))
    )
    (comp (ref "LED-8")
      (value "SK6812-E-REVERSE")
      (footprint "eagle-import:SK6812-E-MILL")
      (libsource (lib "eagle-import") (part "SK6812-E-REVERSE"))
    )
    (comp (ref "LED-CL")
      (value "SK6812-E-REVERSE")
      (footprint "eagle-import:SK6812-E-MILL")
      (libsource (lib "eagle-import") (part "SK6812-E-REVERSE"))
    )
    (comp (ref "LM1117")
      (value "AMS1117-3.3")
      (footprint "eagle-import:SOT223")
      (libsource (lib "eagle-import") (part "V_REG_LM1117SOT223"))
    )
    (comp (ref "LOGO1")
      (value "OSHW-LOGOL")
      (footprint "eagle-import:OSHW-LOGO-L")
      (libsource (lib "eagle-import") (part "OSHW-LOGOL"))
    )
    (comp (ref "M1")
      (value "M25C")
      (footprint "eagle-import:8-SOIC")
      (libsource (lib "eagle-import") (part "M25C"))
    )
    (comp (ref "PTC")
      (value "PTC_ASMD1206-150")
      (footprint "eagle-import:SMD_PTC")
      (libsource (lib "eagle-import") (part "PTC_ASMD1206"))
    )
    (comp (ref "R1")
      (value "5.1K")
      (footprint "eagle-import:R0603")
      (libsource (lib "eagle-import") (part "R-EU_R0603"))
    )
    (comp (ref "R2")
      (value "5.1K")
      (footprint "eagle-import:R0603")
      (libsource (lib "eagle-import") (part "R-EU_R0603"))
    )
    (comp (ref "R3")
      (value "150K")
      (footprint "eagle-import:R0603")
      (libsource (lib "eagle-import") (part "R-EU_R0603"))
    )
    (comp (ref "R4")
      (value "75K")
      (footprint "eagle-import:R0603")
      (libsource (lib "eagle-import") (part "R-EU_R0603"))
    )
    (comp (ref "R5")
      (value "1000K")
      (footprint "eagle-import:0603")
      (libsource (lib "eagle-import") (part "75KOHM-0603-1/10W-1%"))
    )
    (comp (ref "R6")
      (value "220")
      (footprint "eagle-import:R0603")
      (libsource (lib "eagle-import") (part "R-EU_R0603"))
    )
    (comp (ref "R7")
      (value "470")
      (footprint "eagle-import:R0603")
      (libsource (lib "eagle-import") (part "R-EU_R0603"))
    )
    (comp (ref "R8")
      (value "5.1K")
      (footprint "eagle-import:R0603")
      (libsource (lib "eagle-import") (part "R-EU_R0603"))
    )
    (comp (ref "R9")
      (value "5.1K")
      (footprint "eagle-import:R0603")
      (libsource (lib "eagle-import") (part "R-EU_R0603"))
    )
    (comp (ref "S1")
      (value "MOMENTARY-SWITCH-SPST-1")
      (footprint "eagle-import:SKRKAEE020")
      (libsource (lib "eagle-import") (part "MOMENTARY-SWITCH-SPST-1"))
    )
    (comp (ref "S2")
      (value "MOMENTARY-SWITCH-SPST-1")
      (footprint "eagle-import:SKRKAEE020")
      (libsource (lib "eagle-import") (part "MOMENTARY-SWITCH-SPST-1"))
    )
    (comp (ref "S3")
      (value "BOOT")
      (footprint "eagle-import:TACTILE_SWITCH_SMD_5.2MM")
      (libsource (lib "eagle-import") (part "MOMENTARY-SWITCH-SPST-SMD-5.2-TALL-REDUNDANT"))
    )
    (comp (ref "S4")
      (value "BOOT")
      (footprint "eagle-import:TACTILE_SWITCH_SMD_5.2MM")
      (libsource (lib "eagle-import") (part "MOMENTARY-SWITCH-SPST-SMD-5.2-TALL-REDUNDANT"))
    )
    (comp (ref "TVS")
      (value "TVS_SMF9.0CA")
      (footprint "eagle-import:SOD123FL-BI")
      (libsource (lib "eagle-import") (part "TVS_SMF9.0CA"))
    )
    (comp (ref "U$3")
      (value "MICROMOD-LOGO")
      (footprint "eagle-import:MICROMOD-LOGO")
      (libsource (lib "eagle-import") (part "MICROMOD-LOGO"))
    )
    (comp (ref "U$5")
      (value "SPARKFUN_LOGO0.2")
      (footprint "eagle-import:SFE_LOGO_NAME_FLAME_.2")
      (libsource (lib "eagle-import") (part "SPARKFUN_LOGO0.2"))
    )
    (comp (ref "U$6")
      (value "QMK_LOGO")
      (footprint "eagle-import:QMK_LOGO")
      (libsource (lib "eagle-import") (part "QMK_LOGO"))
    )
    (comp (ref "U$8")
      (value "TECSMITH-LOGOLONG")
      (footprint "eagle-import:TECSMITH-NAME")
      (libsource (lib "eagle-import") (part "TECSMITH-LOGOLONG"))
    )
    (comp (ref "U$20")
      (value "FIDUCIAL")
      (footprint "eagle-import:FIDUCIAL")
      (libsource (lib "eagle-import") (part "FIDUCIAL"))
    )
    (comp (ref "U$21")
      (value "FIDUCIAL")
      (footprint "eagle-import:FIDUCIAL")
      (libsource (lib "eagle-import") (part "FIDUCIAL"))
    )
    (comp (ref "U$22")
      (value "FIDUCIAL")
      (footprint "eagle-import:FIDUCIAL")
      (libsource (lib "eagle-import") (part "FIDUCIAL"))
    )
    (comp (ref "U$24")
      (value "FOOTPRINT-BAKENEKO60")
      (footprint "eagle-import:FOOTPRINT-BAKENEKO60")
      (libsource (lib "eagle-import") (part "FOOTPRINT-BAKENEKO60"))
    )
    (comp (ref "U$27")
      (value "FOOTPRINT-DIMS-GH60")
      (footprint "eagle-import:FOOTPRINT-DIMS-GH60")
      (libsource (lib "eagle-import") (part "FOOTPRINT-DIMS-GH60"))
    )
    (comp (ref "X1")
      (value "MICROMOD-2222-C")
      (footprint "eagle-import:M.2-CONNECTOR-E")
      (libsource (lib "eagle-import") (part "MICROMOD-2222-C"))
    )
  )
  (nets
    (net (code "1") (name "52") (class "Default")
      (node (ref "J-52") (pin "2") (pinfunction "2_2") (pintype "passive"))
      (node (ref "X1") (pin "52") (pinfunction "AUD_LRCLK_52") (pintype "bidirectional"))
    )
    (net (code "2") (name "63") (class "Default")
      (node (ref "J-63") (pin "1") (pinfunction "1_1") (pintype "passive"))
      (node (ref "X1") (pin "63") (pinfunction "G10/ADC_D+/CAM_VSYNC_63") (pintype "bidirectional"))
    )
    (net (code "3") (name "BOOT") (class "Default")
      (node (ref "D80") (pin "3") (pinfunction "C_3") (pintype "passive"))
      (node (ref "J-BOOT") (pin "1") (pinfunction "1_1") (pintype "passive"))
      (node (ref "R9") (pin "1") (pinfunction "1_1") (pintype "passive"))
      (node (ref "S3") (pin "3") (pinfunction "2_3") (pintype "passive"))
      (node (ref "S3") (pin "4") (pinfunction "2_4") (pintype "passive"))
      (node (ref "S4") (pin "3") (pinfunction "2_3") (pintype "passive"))
      (node (ref "S4") (pin "4") (pinfunction "2_4") (pintype "passive"))
    )
    (net (code "4") (name "D+") (class "Default")
      (node (ref "ESD") (pin "P$1") (pinfunction "P$1_P$1") (pintype "bidirectional"))
      (node (ref "ESD") (pin "P$6") (pinfunction "P$6_P$6") (pintype "bidirectional"))
      (node (ref "J-UBS") (pin "A6") (pinfunction "D+_A6") (pintype "bidirectional"))
      (node (ref "J-UBS") (pin "B6") (pinfunction "D+_B6") (pintype "bidirectional"))
      (node (ref "J-UDB") (pin "3") (pinfunction "D+_3") (pintype "passive"))
      (node (ref "X1") (pin "3") (pinfunction "USB_D+_3") (pintype "bidirectional"))
    )
    (net (code "5") (name "D-") (class "Default")
      (node (ref "ESD") (pin "P$3") (pinfunction "P$3_P$3") (pintype "bidirectional"))
      (node (ref "ESD") (pin "P$4") (pinfunction "P$4_P$4") (pintype "bidirectional"))
      (node (ref "J-UBS") (pin "A7") (pinfunction "D-_A7") (pintype "bidirectional"))
      (node (ref "J-UBS") (pin "B7") (pinfunction "D-_B7") (pintype "bidirectional"))
      (node (ref "J-UDB") (pin "2") (pinfunction "D-_2") (pintype "passive"))
      (node (ref "X1") (pin "5") (pinfunction "USB_D-_5") (pintype "bidirectional"))
    )
    (net (code "6") (name "EE_CS") (class "Default")
      (node (ref "M1") (pin "1") (pinfunction "~{CS}_1") (pintype "bidirectional"))
      (node (ref "X1") (pin "55") (pinfunction "SPI_~{CS}_55") (pintype "bidirectional"))
    )
    (net (code "7") (name "GND") (class "Default")
      (node (ref "74AH") (pin "1") (pinfunction "~{OE}_1") (pintype "input"))
      (node (ref "74AH") (pin "3") (pinfunction "3_GND_3") (pintype "power_in"))
      (node (ref "C01") (pin "2") (pinfunction "2_2") (pintype "passive"))
      (node (ref "C02") (pin "2") (pinfunction "2_2") (pintype "passive"))
      (node (ref "C03") (pin "2") (pinfunction "2_2") (pintype "passive"))
      (node (ref "C04") (pin "2") (pinfunction "2_2") (pintype "passive"))
      (node (ref "C05") (pin "2") (pinfunction "2_2") (pintype "passive"))
      (node (ref "C06") (pin "2") (pinfunction "2_2") (pintype "passive"))
      (node (ref "C07") (pin "2") (pinfunction "2_2") (pintype "passive"))
      (node (ref "C08") (pin "2") (pinfunction "2_2") (pintype "passive"))
      (node (ref "C09") (pin "2") (pinfunction "2_2") (pintype "passive"))
      (node (ref "C10") (pin "2") (pinfunction "2_2") (pintype "passive"))
      (node (ref "C11") (pin "2") (pinfunction "2_2") (pintype "passive"))
      (node (ref "C12") (pin "2") (pinfunction "2_2") (pintype "passive"))
      (node (ref "C13") (pin "2") (pinfunction "2_2") (pintype "passive"))
      (node (ref "C14") (pin "2") (pinfunction "2_2") (pintype "passive"))
      (node (ref "ESD") (pin "P$2") (pinfunction "P$2_P$2") (pintype "bidirectional"))
      (node (ref "H5") (pin "1") (pinfunction "1_1") (pintype "bidirectional"))
      (node (ref "J-52") (pin "1") (pinfunction "1_1") (pintype "passive"))
      (node (ref "J-BOOT") (pin "2") (pinfunction "2_2") (pintype "passive"))
      (node (ref "J-LED") (pin "1") (pinfunction "1_1") (pintype "passive"))
      (node (ref "J-UBS") (pin "GND") (pinfunction "GND_GND") (pintype "bidirectional"))
      (node (ref "J-UBS") (pin "GND2") (pinfunction "GND_GND2") (pintype "bidirectional"))
      (node (ref "J-UDB") (pin "4") (pinfunction "GND_4") (pintype "power_in"))
      (node (ref "LED-5") (pin "3-GND") (pinfunction "3_GND_3-GND") (pintype "power_in"))
      (node (ref "LED-6") (pin "3-GND") (pinfunction "3_GND_3-GND") (pintype "power_in"))
      (node (ref "LED-7") (pin "3-GND") (pinfunction "3_GND_3-GND") (pintype "power_in"))
      (node (ref "LED-8") (pin "3-GND") (pinfunction "3_GND_3-GND") (pintype "power_in"))
      (node (ref "LED-CL") (pin "3-GND") (pinfunction "3_GND_3-GND") (pintype "power_in"))
      (node (ref "LM1117") (pin "1") (pinfunction "ADJ_1") (pintype "input"))
      (node (ref "M1") (pin "4") (pinfunction "GND_4") (pintype "bidirectional"))
      (node (ref "R1") (pin "2") (pinfunction "2_2") (pintype "passive"))
      (node (ref "R2") (pin "2") (pinfunction "2_2") (pintype "passive"))
      (node (ref "R4") (pin "1") (pinfunction "1_1") (pintype "passive"))
      (node (ref "R5") (pin "1") (pinfunction "1_1") (pintype "passive"))
      (node (ref "R8") (pin "1") (pinfunction "1_1") (pintype "passive"))
      (node (ref "S1") (pin "1") (pinfunction "1_1") (pintype "passive"))
      (node (ref "S2") (pin "1") (pinfunction "1_1") (pintype "passive"))
      (node (ref "S3") (pin "1") (pinfunction "1_1") (pintype "passive"))
      (node (ref "S3") (pin "2") (pinfunction "1_2") (pintype "passive"))
      (node (ref "S4") (pin "1") (pinfunction "1_1") (pintype "passive"))
      (node (ref "S4") (pin "2") (pinfunction "1_2") (pintype "passive"))
      (node (ref "TVS") (pin "P$2") (pinfunction "2_P$2") (pintype "passive"))
      (node (ref "X1") (pin "1") (pinfunction "GND_1") (pintype "bidirectional"))
      (node (ref "X1") (pin "33") (pinfunction "GND_33") (pintype "bidirectional"))
      (node (ref "X1") (pin "36") (pinfunction "GND_36") (pintype "bidirectional"))
      (node (ref "X1") (pin "39") (pinfunction "GND_39") (pintype "bidirectional"))
      (node (ref "X1") (pin "45") (pinfunction "GND_45") (pintype "bidirectional"))
      (node (ref "X1") (pin "7") (pinfunction "GND_7") (pintype "bidirectional"))
      (node (ref "X1") (pin "75") (pinfunction "GND_75") (pintype "bidirectional"))
    )
    (net (code "8") (name "GROUND") (class "Default")
      (node (ref "C06") (pin "1") (pinfunction "1_1") (pintype "passive"))
      (node (ref "J-UBS") (pin "SHLD1") (pinfunction "SHLD_SHLD1") (pintype "bidirectional"))
      (node (ref "J-UBS") (pin "SHLD2") (pinfunction "SHLD_SHLD2") (pintype "bidirectional"))
      (node (ref "J-UBS") (pin "SHLD3") (pinfunction "SHLD_SHLD3") (pintype "bidirectional"))
      (node (ref "J-UBS") (pin "SHLD4") (pinfunction "SHLD_SHLD4") (pintype "bidirectional"))
      (node (ref "J-UBS") (pin "SHLD5") (pinfunction "SHLD_SHLD5") (pintype "bidirectional"))
      (node (ref "J-UBS") (pin "SHLD6") (pinfunction "SHLD_SHLD6") (pintype "bidirectional"))
      (node (ref "J-UBS") (pin "SHLD7") (pinfunction "SHLD_SHLD7") (pintype "bidirectional"))
      (node (ref "J-UBS") (pin "SHLD8") (pinfunction "SHLD_SHLD8") (pintype "bidirectional"))
      (node (ref "JP-GND") (pin "2") (pinfunction "2_2") (pintype "passive"))
      (node (ref "R5") (pin "2") (pinfunction "2_2") (pintype "passive"))
    )
    (net (code "9") (name "LED") (class "Default")
      (node (ref "R6") (pin "2") (pinfunction "2_2") (pintype "passive"))
      (node (ref "X1") (pin "32") (pinfunction "PWM0_32") (pintype "bidirectional"))
    )
    (net (code "10") (name "MISO") (class "Default")
      (node (ref "M1") (pin "2") (pinfunction "DO_2") (pintype "bidirectional"))
      (node (ref "X1") (pin "61") (pinfunction "SPI_SDI_61") (pintype "bidirectional"))
    )
    (net (code "11") (name "MOSI") (class "Default")
      (node (ref "M1") (pin "5") (pinfunction "DIO_5") (pintype "bidirectional"))
      (node (ref "X1") (pin "59") (pinfunction "SPI_SDO_59") (pintype "bidirectional"))
    )
    (net (code "12") (name "MX0") (class "Default")
      (node (ref "D01") (pin "C") (pinfunction "C_C") (pintype "passive"))
      (node (ref "D09") (pin "C") (pinfunction "C_C") (pintype "passive"))
      (node (ref "D15") (pin "C") (pinfunction "C_C") (pintype "passive"))
      (node (ref "D23") (pin "C") (pinfunction "C_C") (pintype "passive"))
      (node (ref "D29") (pin "C") (pinfunction "C_C") (pintype "passive"))
      (node (ref "D37") (pin "C") (pinfunction "C_C") (pintype "passive"))
      (node (ref "D42") (pin "C") (pinfunction "C_C") (pintype "passive"))
      (node (ref "D50") (pin "C") (pinfunction "C_C") (pintype "passive"))
      (node (ref "D55") (pin "C") (pinfunction "C_C") (pintype "passive"))
      (node (ref "X1") (pin "47") (pinfunction "PWM1_47") (pintype "bidirectional"))
    )
    (net (code "13") (name "MX1") (class "Default")
      (node (ref "D02") (pin "C") (pinfunction "C_C") (pintype "passive"))
      (node (ref "D10") (pin "C") (pinfunction "C_C") (pintype "passive"))
      (node (ref "D16") (pin "C") (pinfunction "C_C") (pintype "passive"))
      (node (ref "D24") (pin "C") (pinfunction "C_C") (pintype "passive"))
      (node (ref "D30") (pin "C") (pinfunction "C_C") (pintype "passive"))
      (node (ref "D38") (pin "C") (pinfunction "C_C") (pintype "passive"))
      (node (ref "D43") (pin "C") (pinfunction "C_C") (pintype "passive"))
      (node (ref "D51") (pin "C") (pinfunction "C_C") (pintype "passive"))
      (node (ref "D56") (pin "C") (pinfunction "C_C") (pintype "passive"))
      (node (ref "X1") (pin "19") (pinfunction "RX1_19") (pintype "bidirectional"))
    )
    (net (code "14") (name "MX2") (class "Default")
      (node (ref "D03") (pin "C") (pinfunction "C_C") (pintype "passive"))
      (node (ref "D11") (pin "C") (pinfunction "C_C") (pintype "passive"))
      (node (ref "D17") (pin "C") (pinfunction "C_C") (pintype "passive"))
      (node (ref "D25") (pin "C") (pinfunction "C_C") (pintype "passive"))
      (node (ref "D31") (pin "C") (pinfunction "C_C") (pintype "passive"))
      (node (ref "D39") (pin "C") (pinfunction "C_C") (pintype "passive"))
      (node (ref "D44") (pin "C") (pinfunction "C_C") (pintype "passive"))
      (node (ref "D52") (pin "C") (pinfunction "C_C") (pintype "passive"))
      (node (ref "D57") (pin "C") (pinfunction "C_C") (pintype "passive"))
      (node (ref "X1") (pin "17") (pinfunction "TX1_17") (pintype "bidirectional"))
    )
    (net (code "15") (name "MX3") (class "Default")
      (node (ref "D04") (pin "C") (pinfunction "C_C") (pintype "passive"))
      (node (ref "D12") (pin "C") (pinfunction "C_C") (pintype "passive"))
      (node (ref "D18") (pin "C") (pinfunction "C_C") (pintype "passive"))
      (node (ref "D26") (pin "C") (pinfunction "C_C") (pintype "passive"))
      (node (ref "D32") (pin "C") (pinfunction "C_C") (pintype "passive"))
      (node (ref "D40") (pin "C") (pinfunction "C_C") (pintype "passive"))
      (node (ref "D45") (pin "C") (pinfunction "C_C") (pintype "passive"))
      (node (ref "D53") (pin "C") (pinfunction "C_C") (pintype "passive"))
      (node (ref "D58") (pin "C") (pinfunction "C_C") (pintype "passive"))
      (node (ref "X1") (pin "18") (pinfunction "D1/CAM_TRIG_18") (pintype "bidirectional"))
    )
    (net (code "16") (name "MX4") (class "Default")
      (node (ref "D05") (pin "C") (pinfunction "C_C") (pintype "passive"))
      (node (ref "D13") (pin "C") (pinfunction "C_C") (pintype "passive"))
      (node (ref "D19") (pin "C") (pinfunction "C_C") (pintype "passive"))
      (node (ref "D27") (pin "C") (pinfunction "C_C") (pintype "passive"))
      (node (ref "D33") (pin "C") (pinfunction "C_C") (pintype "passive"))
      (node (ref "D46") (pin "C") (pinfunction "C_C") (pintype "passive"))
      (node (ref "D59") (pin "C") (pinfunction "C_C") (pintype "passive"))
      (node (ref "D63") (pin "C") (pinfunction "C_C") (pintype "passive"))
      (node (ref "D64") (pin "C") (pinfunction "C_C") (pintype "passive"))
      (node (ref "X1") (pin "16") (pinfunction "I2C_~{INT}_16") (pintype "bidirectional"))
    )
    (net (code "17") (name "MX5") (class "Default")
      (node (ref "D06") (pin "C") (pinfunction "C_C") (pintype "passive"))
      (node (ref "D20") (pin "C") (pinfunction "C_C") (pintype "passive"))
      (node (ref "D34") (pin "C") (pinfunction "C_C") (pintype "passive"))
      (node (ref "D47") (pin "C") (pinfunction "C_C") (pintype "passive"))
      (node (ref "D54") (pin "C") (pinfunction "C_C") (pintype "passive"))
      (node (ref "D60") (pin "C") (pinfunction "C_C") (pintype "passive"))
      (node (ref "D65") (pin "C") (pinfunction "C_C") (pintype "passive"))
      (node (ref "D66") (pin "C") (pinfunction "C_C") (pintype "passive"))
      (node (ref "D67") (pin "C") (pinfunction "C_C") (pintype "passive"))
      (node (ref "X1") (pin "14") (pinfunction "I2C_SCL_14") (pintype "bidirectional"))
    )
    (net (code "18") (name "MX6") (class "Default")
      (node (ref "D07") (pin "C") (pinfunction "C_C") (pintype "passive"))
      (node (ref "D14") (pin "C") (pinfunction "C_C") (pintype "passive"))
      (node (ref "D21") (pin "C") (pinfunction "C_C") (pintype "passive"))
      (node (ref "D28") (pin "C") (pinfunction "C_C") (pintype "passive"))
      (node (ref "D35") (pin "C") (pinfunction "C_C") (pintype "passive"))
      (node (ref "D41") (pin "C") (pinfunction "C_C") (pintype "passive"))
      (node (ref "D48") (pin "C") (pinfunction "C_C") (pintype "passive"))
      (node (ref "D61") (pin "C") (pinfunction "C_C") (pintype "passive"))
      (node (ref "X1") (pin "12") (pinfunction "I2C_SDA_12") (pintype "bidirectional"))
    )
    (net (code "19") (name "MX7") (class "Default")
      (node (ref "D08") (pin "C") (pinfunction "C_C") (pintype "passive"))
      (node (ref "D22") (pin "C") (pinfunction "C_C") (pintype "passive"))
      (node (ref "D36") (pin "C") (pinfunction "C_C") (pintype "passive"))
      (node (ref "D49") (pin "C") (pinfunction "C_C") (pintype "passive"))
      (node (ref "D62") (pin "C") (pinfunction "C_C") (pintype "passive"))
      (node (ref "X1") (pin "10") (pinfunction "D0_10") (pintype "bidirectional"))
    )
    (net (code "20") (name "MY0") (class "Default")
      (node (ref "S_1") (pin "2@1") (pinfunction "1_2@1") (pintype "passive"))
      (node (ref "S_1") (pin "2@2") (pinfunction "1_2@2") (pintype "passive"))
      (node (ref "S_2") (pin "2@1") (pinfunction "1_2@1") (pintype "passive"))
      (node (ref "S_2") (pin "2@2") (pinfunction "1_2@2") (pintype "passive"))
      (node (ref "S_3") (pin "2@1") (pinfunction "1_2@1") (pintype "passive"))
      (node (ref "S_3") (pin "2@2") (pinfunction "1_2@2") (pintype "passive"))
      (node (ref "S_4") (pin "2@1") (pinfunction "1_2@1") (pintype "passive"))
      (node (ref "S_4") (pin "2@2") (pinfunction "1_2@2") (pintype "passive"))
      (node (ref "S_5") (pin "2@1") (pinfunction "1_2@1") (pintype "passive"))
      (node (ref "S_5") (pin "2@2") (pinfunction "1_2@2") (pintype "passive"))
      (node (ref "S_6") (pin "2@1") (pinfunction "1_2@1") (pintype "passive"))
      (node (ref "S_6") (pin "2@2") (pinfunction "1_2@2") (pintype "passive"))
      (node (ref "S_7") (pin "2@1") (pinfunction "1_2@1") (pintype "passive"))
      (node (ref "S_7") (pin "2@2") (pinfunction "1_2@2") (pintype "passive"))
      (node (ref "S_ESC") (pin "2@1") (pinfunction "1_2@1") (pintype "passive"))
      (node (ref "S_ESC") (pin "2@2") (pinfunction "1_2@2") (pintype "passive"))
      (node (ref "X1") (pin "56") (pinfunction "AUD_OUT/CAM_MCLK_56") (pintype "bidirectional"))
    )
    (net (code "21") (name "MY1") (class "Default")
      (node (ref "S_E") (pin "2@1") (pinfunction "1_2@1") (pintype "passive"))
      (node (ref "S_E") (pin "2@2") (pinfunction "1_2@2") (pintype "passive"))
      (node (ref "S_Q") (pin "2@1") (pinfunction "1_2@1") (pintype "passive"))
      (node (ref "S_Q") (pin "2@2") (pinfunction "1_2@2") (pintype "passive"))
      (node (ref "S_R") (pin "2@1") (pinfunction "1_2@1") (pintype "passive"))
      (node (ref "S_R") (pin "2@2") (pinfunction "1_2@2") (pintype "passive"))
      (node (ref "S_T") (pin "2@1") (pinfunction "1_2@1") (pintype "passive"))
      (node (ref "S_T") (pin "2@2") (pinfunction "1_2@2") (pintype "passive"))
      (node (ref "S_TAB") (pin "2@1") (pinfunction "1_2@1") (pintype "passive"))
      (node (ref "S_TAB") (pin "2@2") (pinfunction "1_2@2") (pintype "passive"))
      (node (ref "S_U") (pin "2@1") (pinfunction "1_2@1") (pintype "passive"))
      (node (ref "S_U") (pin "2@2") (pinfunction "1_2@2") (pintype "passive"))
      (node (ref "S_W") (pin "2@1") (pinfunction "1_2@1") (pintype "passive"))
      (node (ref "S_W") (pin "2@2") (pinfunction "1_2@2") (pintype "passive"))
      (node (ref "S_Y") (pin "2@1") (pinfunction "1_2@1") (pintype "passive"))
      (node (ref "S_Y") (pin "2@2") (pinfunction "1_2@2") (pintype "passive"))
      (node (ref "X1") (pin "54") (pinfunction "AUD_IN/CAM_PCLK_54") (pintype "bidirectional"))
    )
    (net (code "22") (name "MY2") (class "Default")
      (node (ref "S_A") (pin "2@1") (pinfunction "1_2@1") (pintype "passive"))
      (node (ref "S_A") (pin "2@2") (pinfunction "1_2@2") (pintype "passive"))
      (node (ref "S_CAPS") (pin "2@1") (pinfunction "1_2@1") (pintype "passive"))
      (node (ref "S_CAPS") (pin "2@2") (pinfunction "1_2@2") (pintype "passive"))
      (node (ref "S_CAPS2") (pin "1") (pinfunction "2_1") (pintype "passive"))
      (node (ref "S_D") (pin "2@1") (pinfunction "1_2@1") (pintype "passive"))
      (node (ref "S_D") (pin "2@2") (pinfunction "1_2@2") (pintype "passive"))
      (node (ref "S_F") (pin "2@1") (pinfunction "1_2@1") (pintype "passive"))
      (node (ref "S_F") (pin "2@2") (pinfunction "1_2@2") (pintype "passive"))
      (node (ref "S_G") (pin "2@1") (pinfunction "1_2@1") (pintype "passive"))
      (node (ref "S_G") (pin "2@2") (pinfunction "1_2@2") (pintype "passive"))
      (node (ref "S_H") (pin "2@1") (pinfunction "1_2@1") (pintype "passive"))
      (node (ref "S_H") (pin "2@2") (pinfunction "1_2@2") (pintype "passive"))
      (node (ref "S_J") (pin "2@1") (pinfunction "1_2@1") (pintype "passive"))
      (node (ref "S_J") (pin "2@2") (pinfunction "1_2@2") (pintype "passive"))
      (node (ref "S_S") (pin "2@1") (pinfunction "1_2@1") (pintype "passive"))
      (node (ref "S_S") (pin "2@2") (pinfunction "1_2@2") (pintype "passive"))
      (node (ref "X1") (pin "50") (pinfunction "AUD_BCLK_50") (pintype "bidirectional"))
    )
    (net (code "23") (name "MY3") (class "Default")
      (node (ref "S_B") (pin "2@1") (pinfunction "1_2@1") (pintype "passive"))
      (node (ref "S_B") (pin "2@2") (pinfunction "1_2@2") (pintype "passive"))
      (node (ref "S_C") (pin "2@1") (pinfunction "1_2@1") (pintype "passive"))
      (node (ref "S_C") (pin "2@2") (pinfunction "1_2@2") (pintype "passive"))
      (node (ref "S_LSFT") (pin "2@1") (pinfunction "1_2@1") (pintype "passive"))
      (node (ref "S_LSFT") (pin "2@2") (pinfunction "1_2@2") (pintype "passive"))
      (node (ref "S_LSFT2") (pin "2@1") (pinfunction "1_2@1") (pintype "passive"))
      (node (ref "S_LSFT2") (pin "2@2") (pinfunction "1_2@2") (pintype "passive"))
      (node (ref "S_N") (pin "2@1") (pinfunction "1_2@1") (pintype "passive"))
      (node (ref "S_N") (pin "2@2") (pinfunction "1_2@2") (pintype "passive"))
      (node (ref "S_NUBS") (pin "2@1") (pinfunction "1_2@1") (pintype "passive"))
      (node (ref "S_NUBS") (pin "2@2") (pinfunction "1_2@2") (pintype "passive"))
      (node (ref "S_V") (pin "2@1") (pinfunction "1_2@1") (pintype "passive"))
      (node (ref "S_V") (pin "2@2") (pinfunction "1_2@2") (pintype "passive"))
      (node (ref "S_X") (pin "2@1") (pinfunction "1_2@1") (pintype "passive"))
      (node (ref "S_X") (pin "2@2") (pinfunction "1_2@2") (pintype "passive"))
      (node (ref "S_Z") (pin "2@1") (pinfunction "1_2@1") (pintype "passive"))
      (node (ref "S_Z") (pin "2@2") (pinfunction "1_2@2") (pintype "passive"))
      (node (ref "X1") (pin "46") (pinfunction "G3/BUS3_46") (pintype "bidirectional"))
    )
    (net (code "24") (name "MY4") (class "Default")
      (node (ref "S_APP") (pin "2@1") (pinfunction "1_2@1") (pintype "passive"))
      (node (ref "S_APP") (pin "2@2") (pinfunction "1_2@2") (pintype "passive"))
      (node (ref "S_FN1") (pin "2@1") (pinfunction "1_2@1") (pintype "passive"))
      (node (ref "S_FN1") (pin "2@2") (pinfunction "1_2@2") (pintype "passive"))
      (node (ref "S_LALT") (pin "2@1") (pinfunction "1_2@1") (pintype "passive"))
      (node (ref "S_LALT") (pin "2@2") (pinfunction "1_2@2") (pintype "passive"))
      (node (ref "S_LALT_2") (pin "1@1") (pinfunction "2_1@1") (pintype "passive"))
      (node (ref "S_LALT_2") (pin "1@2") (pinfunction "2_1@2") (pintype "passive"))
      (node (ref "S_LCTL") (pin "2@1") (pinfunction "1_2@1") (pintype "passive"))
      (node (ref "S_LCTL") (pin "2@2") (pinfunction "1_2@2") (pintype "passive"))
      (node (ref "S_LCTL_2") (pin "1@1") (pinfunction "2_1@1") (pintype "passive"))
      (node (ref "S_LCTL_2") (pin "1@2") (pinfunction "2_1@2") (pintype "passive"))
      (node (ref "S_LGUI") (pin "2@1") (pinfunction "1_2@1") (pintype "passive"))
      (node (ref "S_LGUI") (pin "2@2") (pinfunction "1_2@2") (pintype "passive"))
      (node (ref "S_LGUI_2") (pin "1@1") (pinfunction "2_1@1") (pintype "passive"))
      (node (ref "S_LGUI_2") (pin "1@2") (pinfunction "2_1@2") (pintype "passive"))
      (node (ref "S_RALT") (pin "2@1") (pinfunction "1_2@1") (pintype "passive"))
      (node (ref "S_RALT") (pin "2@2") (pinfunction "1_2@2") (pintype "passive"))
      (node (ref "S_RALT_2") (pin "1@1") (pinfunction "2_1@1") (pintype "passive"))
      (node (ref "S_RALT_2") (pin "1@2") (pinfunction "2_1@2") (pintype "passive"))
      (node (ref "S_RCTL") (pin "2@1") (pinfunction "1_2@1") (pintype "passive"))
      (node (ref "S_RCTL") (pin "2@2") (pinfunction "1_2@2") (pintype "passive"))
      (node (ref "S_RCTL_2") (pin "1@1") (pinfunction "2_1@1") (pintype "passive"))
      (node (ref "S_RCTL_2") (pin "1@2") (pinfunction "2_1@2") (pintype "passive"))
      (node (ref "S_RGUI_2") (pin "1@1") (pinfunction "2_1@1") (pintype "passive"))
      (node (ref "S_RGUI_2") (pin "1@2") (pinfunction "2_1@2") (pintype "passive"))
      (node (ref "S_SPC") (pin "2@1") (pinfunction "1_2@1") (pintype "passive"))
      (node (ref "S_SPC") (pin "2@2") (pinfunction "1_2@2") (pintype "passive"))
      (node (ref "S_SPC_2") (pin "1@1") (pinfunction "2_1@1") (pintype "passive"))
      (node (ref "S_SPC_2") (pin "1@2") (pinfunction "2_1@2") (pintype "passive"))
      (node (ref "X1") (pin "44") (pinfunction "G2/BUS2_44") (pintype "bidirectional"))
    )
    (net (code "25") (name "MY5") (class "Default")
      (node (ref "DIP-SW") (pin "8") (pinfunction "8_8") (pintype "passive"))
      (node (ref "S_0") (pin "2@1") (pinfunction "1_2@1") (pintype "passive"))
      (node (ref "S_0") (pin "2@2") (pinfunction "1_2@2") (pintype "passive"))
      (node (ref "S_8") (pin "2@1") (pinfunction "1_2@1") (pintype "passive"))
      (node (ref "S_8") (pin "2@2") (pinfunction "1_2@2") (pintype "passive"))
      (node (ref "S_9") (pin "2@1") (pinfunction "1_2@1") (pintype "passive"))
      (node (ref "S_9") (pin "2@2") (pinfunction "1_2@2") (pintype "passive"))
      (node (ref "S_BSPC") (pin "2@1") (pinfunction "1_2@1") (pintype "passive"))
      (node (ref "S_BSPC") (pin "2@2") (pinfunction "1_2@2") (pintype "passive"))
      (node (ref "S_BSPC2") (pin "2@1") (pinfunction "1_2@1") (pintype "passive"))
      (node (ref "S_BSPC2") (pin "2@2") (pinfunction "1_2@2") (pintype "passive"))
      (node (ref "S_EQL") (pin "2@1") (pinfunction "1_2@1") (pintype "passive"))
      (node (ref "S_EQL") (pin "2@2") (pinfunction "1_2@2") (pintype "passive"))
      (node (ref "S_MINS") (pin "2@1") (pinfunction "1_2@1") (pintype "passive"))
      (node (ref "S_MINS") (pin "2@2") (pinfunction "1_2@2") (pintype "passive"))
      (node (ref "X1") (pin "42") (pinfunction "G1/BUS1_42") (pintype "bidirectional"))
    )
    (net (code "26") (name "MY6") (class "Default")
      (node (ref "DIP-SW") (pin "7") (pinfunction "7_7") (pintype "passive"))
      (node (ref "S_BSLS") (pin "2@1") (pinfunction "1_2@1") (pintype "passive"))
      (node (ref "S_BSLS") (pin "2@2") (pinfunction "1_2@2") (pintype "passive"))
      (node (ref "S_BSLS2") (pin "2@1") (pinfunction "1_2@1") (pintype "passive"))
      (node (ref "S_BSLS2") (pin "2@2") (pinfunction "1_2@2") (pintype "passive"))
      (node (ref "S_I") (pin "2@1") (pinfunction "1_2@1") (pintype "passive"))
      (node (ref "S_I") (pin "2@2") (pinfunction "1_2@2") (pintype "passive"))
      (node (ref "S_LBRC") (pin "2@1") (pinfunction "1_2@1") (pintype "passive"))
      (node (ref "S_LBRC") (pin "2@2") (pinfunction "1_2@2") (pintype "passive"))
      (node (ref "S_O") (pin "2@1") (pinfunction "1_2@1") (pintype "passive"))
      (node (ref "S_O") (pin "2@2") (pinfunction "1_2@2") (pintype "passive"))
      (node (ref "S_P") (pin "2@1") (pinfunction "1_2@1") (pintype "passive"))
      (node (ref "S_P") (pin "2@2") (pinfunction "1_2@2") (pintype "passive"))
      (node (ref "S_RBRC") (pin "2@1") (pinfunction "1_2@1") (pintype "passive"))
      (node (ref "S_RBRC") (pin "2@2") (pinfunction "1_2@2") (pintype "passive"))
      (node (ref "X1") (pin "40") (pinfunction "G0/BUS0_40") (pintype "bidirectional"))
    )
    (net (code "27") (name "MY7") (class "Default")
      (node (ref "DIP-SW") (pin "6") (pinfunction "6_6") (pintype "passive"))
      (node (ref "S_ENT") (pin "2@1") (pinfunction "1_2@1") (pintype "passive"))
      (node (ref "S_ENT") (pin "2@2") (pinfunction "1_2@2") (pintype "passive"))
      (node (ref "S_ENT2") (pin "2@1") (pinfunction "1_2@1") (pintype "passive"))
      (node (ref "S_ENT2") (pin "2@2") (pinfunction "1_2@2") (pintype "passive"))
      (node (ref "S_K") (pin "2@1") (pinfunction "1_2@1") (pintype "passive"))
      (node (ref "S_K") (pin "2@2") (pinfunction "1_2@2") (pintype "passive"))
      (node (ref "S_L") (pin "2@1") (pinfunction "1_2@1") (pintype "passive"))
      (node (ref "S_L") (pin "2@2") (pinfunction "1_2@2") (pintype "passive"))
      (node (ref "S_QUOT") (pin "2@1") (pinfunction "1_2@1") (pintype "passive"))
      (node (ref "S_QUOT") (pin "2@2") (pinfunction "1_2@2") (pintype "passive"))
      (node (ref "S_SCLN") (pin "2@1") (pinfunction "1_2@1") (pintype "passive"))
      (node (ref "S_SCLN") (pin "2@2") (pinfunction "1_2@2") (pintype "passive"))
      (node (ref "S_SPARE") (pin "2@1") (pinfunction "1_2@1") (pintype "passive"))
      (node (ref "S_SPARE") (pin "2@2") (pinfunction "1_2@2") (pintype "passive"))
      (node (ref "X1") (pin "38") (pinfunction "A1_38") (pintype "bidirectional"))
    )
    (net (code "28") (name "MY8") (class "Default")
      (node (ref "S_COM") (pin "2@1") (pinfunction "1_2@1") (pintype "passive"))
      (node (ref "S_COM") (pin "2@2") (pinfunction "1_2@2") (pintype "passive"))
      (node (ref "S_DOT") (pin "2@1") (pinfunction "1_2@1") (pintype "passive"))
      (node (ref "S_DOT") (pin "2@2") (pinfunction "1_2@2") (pintype "passive"))
      (node (ref "S_FN") (pin "2@1") (pinfunction "1_2@1") (pintype "passive"))
      (node (ref "S_FN") (pin "2@2") (pinfunction "1_2@2") (pintype "passive"))
      (node (ref "S_M") (pin "2@1") (pinfunction "1_2@1") (pintype "passive"))
      (node (ref "S_M") (pin "2@2") (pinfunction "1_2@2") (pintype "passive"))
      (node (ref "S_RSFT") (pin "2@1") (pinfunction "1_2@1") (pintype "passive"))
      (node (ref "S_RSFT") (pin "2@2") (pinfunction "1_2@2") (pintype "passive"))
      (node (ref "S_RSFT2") (pin "2@1") (pinfunction "1_2@1") (pintype "passive"))
      (node (ref "S_RSFT2") (pin "2@2") (pinfunction "1_2@2") (pintype "passive"))
      (node (ref "S_SLSH") (pin "2@1") (pinfunction "1_2@1") (pintype "passive"))
      (node (ref "S_SLSH") (pin "2@2") (pinfunction "1_2@2") (pintype "passive"))
      (node (ref "X1") (pin "34") (pinfunction "A0_34") (pintype "bidirectional"))
    )
    (net (code "29") (name "Net-(74AH-A_DIN)") (class "Default")
      (node (ref "74AH") (pin "2") (pinfunction "A_DIN_2") (pintype "input"))
      (node (ref "R6") (pin "1") (pinfunction "1_1") (pintype "passive"))
    )
    (net (code "30") (name "Net-(74AH-Y_DOUT)") (class "Default")
      (node (ref "74AH") (pin "4") (pinfunction "Y_DOUT_4") (pintype "output"))
      (node (ref "R7") (pin "2") (pinfunction "2_2") (pintype "passive"))
    )
    (net (code "31") (name "Net-(D01-PadA)") (class "Default")
      (node (ref "D01") (pin "A") (pinfunction "A_A") (pintype "passive"))
      (node (ref "S_ESC") (pin "1@1") (pinfunction "2_1@1") (pintype "passive"))
      (node (ref "S_ESC") (pin "1@2") (pinfunction "2_1@2") (pintype "passive"))
    )
    (net (code "32") (name "Net-(D02-PadA)") (class "Default")
      (node (ref "D02") (pin "A") (pinfunction "A_A") (pintype "passive"))
      (node (ref "S_1") (pin "1@1") (pinfunction "2_1@1") (pintype "passive"))
      (node (ref "S_1") (pin "1@2") (pinfunction "2_1@2") (pintype "passive"))
    )
    (net (code "33") (name "Net-(D03-PadA)") (class "Default")
      (node (ref "D03") (pin "A") (pinfunction "A_A") (pintype "passive"))
      (node (ref "S_2") (pin "1@1") (pinfunction "2_1@1") (pintype "passive"))
      (node (ref "S_2") (pin "1@2") (pinfunction "2_1@2") (pintype "passive"))
    )
    (net (code "34") (name "Net-(D04-PadA)") (class "Default")
      (node (ref "D04") (pin "A") (pinfunction "A_A") (pintype "passive"))
      (node (ref "S_3") (pin "1@1") (pinfunction "2_1@1") (pintype "passive"))
      (node (ref "S_3") (pin "1@2") (pinfunction "2_1@2") (pintype "passive"))
    )
    (net (code "35") (name "Net-(D05-PadA)") (class "Default")
      (node (ref "D05") (pin "A") (pinfunction "A_A") (pintype "passive"))
      (node (ref "S_4") (pin "1@1") (pinfunction "2_1@1") (pintype "passive"))
      (node (ref "S_4") (pin "1@2") (pinfunction "2_1@2") (pintype "passive"))
    )
    (net (code "36") (name "Net-(D06-PadA)") (class "Default")
      (node (ref "D06") (pin "A") (pinfunction "A_A") (pintype "passive"))
      (node (ref "S_5") (pin "1@1") (pinfunction "2_1@1") (pintype "passive"))
      (node (ref "S_5") (pin "1@2") (pinfunction "2_1@2") (pintype "passive"))
    )
    (net (code "37") (name "Net-(D07-PadA)") (class "Default")
      (node (ref "D07") (pin "A") (pinfunction "A_A") (pintype "passive"))
      (node (ref "S_6") (pin "1@1") (pinfunction "2_1@1") (pintype "passive"))
      (node (ref "S_6") (pin "1@2") (pinfunction "2_1@2") (pintype "passive"))
    )
    (net (code "38") (name "Net-(D08-PadA)") (class "Default")
      (node (ref "D08") (pin "A") (pinfunction "A_A") (pintype "passive"))
      (node (ref "S_7") (pin "1@1") (pinfunction "2_1@1") (pintype "passive"))
      (node (ref "S_7") (pin "1@2") (pinfunction "2_1@2") (pintype "passive"))
    )
    (net (code "39") (name "Net-(D09-PadA)") (class "Default")
      (node (ref "D09") (pin "A") (pinfunction "A_A") (pintype "passive"))
      (node (ref "S_8") (pin "1@1") (pinfunction "2_1@1") (pintype "passive"))
      (node (ref "S_8") (pin "1@2") (pinfunction "2_1@2") (pintype "passive"))
    )
    (net (code "40") (name "Net-(D10-PadA)") (class "Default")
      (node (ref "D10") (pin "A") (pinfunction "A_A") (pintype "passive"))
      (node (ref "S_9") (pin "1@1") (pinfunction "2_1@1") (pintype "passive"))
      (node (ref "S_9") (pin "1@2") (pinfunction "2_1@2") (pintype "passive"))
    )
    (net (code "41") (name "Net-(D11-PadA)") (class "Default")
      (node (ref "D11") (pin "A") (pinfunction "A_A") (pintype "passive"))
      (node (ref "S_0") (pin "1@1") (pinfunction "2_1@1") (pintype "passive"))
      (node (ref "S_0") (pin "1@2") (pinfunction "2_1@2") (pintype "passive"))
    )
    (net (code "42") (name "Net-(D12-PadA)") (class "Default")
      (node (ref "D12") (pin "A") (pinfunction "A_A") (pintype "passive"))
      (node (ref "S_MINS") (pin "1@1") (pinfunction "2_1@1") (pintype "passive"))
      (node (ref "S_MINS") (pin "1@2") (pinfunction "2_1@2") (pintype "passive"))
    )
    (net (code "43") (name "Net-(D13-PadA)") (class "Default")
      (node (ref "D13") (pin "A") (pinfunction "A_A") (pintype "passive"))
      (node (ref "S_EQL") (pin "1@1") (pinfunction "2_1@1") (pintype "passive"))
      (node (ref "S_EQL") (pin "1@2") (pinfunction "2_1@2") (pintype "passive"))
    )
    (net (code "44") (name "Net-(D14-PadA)") (class "Default")
      (node (ref "D14") (pin "A") (pinfunction "A_A") (pintype "passive"))
      (node (ref "S_BSPC") (pin "1@1") (pinfunction "2_1@1") (pintype "passive"))
      (node (ref "S_BSPC") (pin "1@2") (pinfunction "2_1@2") (pintype "passive"))
      (node (ref "S_BSPC2") (pin "1@1") (pinfunction "2_1@1") (pintype "passive"))
      (node (ref "S_BSPC2") (pin "1@2") (pinfunction "2_1@2") (pintype "passive"))
    )
    (net (code "45") (name "Net-(D15-PadA)") (class "Default")
      (node (ref "D15") (pin "A") (pinfunction "A_A") (pintype "passive"))
      (node (ref "S_TAB") (pin "1@1") (pinfunction "2_1@1") (pintype "passive"))
      (node (ref "S_TAB") (pin "1@2") (pinfunction "2_1@2") (pintype "passive"))
    )
    (net (code "46") (name "Net-(D16-PadA)") (class "Default")
      (node (ref "D16") (pin "A") (pinfunction "A_A") (pintype "passive"))
      (node (ref "S_Q") (pin "1@1") (pinfunction "2_1@1") (pintype "passive"))
      (node (ref "S_Q") (pin "1@2") (pinfunction "2_1@2") (pintype "passive"))
    )
    (net (code "47") (name "Net-(D17-PadA)") (class "Default")
      (node (ref "D17") (pin "A") (pinfunction "A_A") (pintype "passive"))
      (node (ref "S_W") (pin "1@1") (pinfunction "2_1@1") (pintype "passive"))
      (node (ref "S_W") (pin "1@2") (pinfunction "2_1@2") (pintype "passive"))
    )
    (net (code "48") (name "Net-(D18-PadA)") (class "Default")
      (node (ref "D18") (pin "A") (pinfunction "A_A") (pintype "passive"))
      (node (ref "S_E") (pin "1@1") (pinfunction "2_1@1") (pintype "passive"))
      (node (ref "S_E") (pin "1@2") (pinfunction "2_1@2") (pintype "passive"))
    )
    (net (code "49") (name "Net-(D19-PadA)") (class "Default")
      (node (ref "D19") (pin "A") (pinfunction "A_A") (pintype "passive"))
      (node (ref "S_R") (pin "1@1") (pinfunction "2_1@1") (pintype "passive"))
      (node (ref "S_R") (pin "1@2") (pinfunction "2_1@2") (pintype "passive"))
    )
    (net (code "50") (name "Net-(D20-PadA)") (class "Default")
      (node (ref "D20") (pin "A") (pinfunction "A_A") (pintype "passive"))
      (node (ref "S_T") (pin "1@1") (pinfunction "2_1@1") (pintype "passive"))
      (node (ref "S_T") (pin "1@2") (pinfunction "2_1@2") (pintype "passive"))
    )
    (net (code "51") (name "Net-(D21-PadA)") (class "Default")
      (node (ref "D21") (pin "A") (pinfunction "A_A") (pintype "passive"))
      (node (ref "S_Y") (pin "1@1") (pinfunction "2_1@1") (pintype "passive"))
      (node (ref "S_Y") (pin "1@2") (pinfunction "2_1@2") (pintype "passive"))
    )
    (net (code "52") (name "Net-(D22-PadA)") (class "Default")
      (node (ref "D22") (pin "A") (pinfunction "A_A") (pintype "passive"))
      (node (ref "S_U") (pin "1@1") (pinfunction "2_1@1") (pintype "passive"))
      (node (ref "S_U") (pin "1@2") (pinfunction "2_1@2") (pintype "passive"))
    )
    (net (code "53") (name "Net-(D23-PadA)") (class "Default")
      (node (ref "D23") (pin "A") (pinfunction "A_A") (pintype "passive"))
      (node (ref "S_I") (pin "1@1") (pinfunction "2_1@1") (pintype "passive"))
      (node (ref "S_I") (pin "1@2") (pinfunction "2_1@2") (pintype "passive"))
    )
    (net (code "54") (name "Net-(D24-PadA)") (class "Default")
      (node (ref "D24") (pin "A") (pinfunction "A_A") (pintype "passive"))
      (node (ref "S_O") (pin "1@1") (pinfunction "2_1@1") (pintype "passive"))
      (node (ref "S_O") (pin "1@2") (pinfunction "2_1@2") (pintype "passive"))
    )
    (net (code "55") (name "Net-(D25-PadA)") (class "Default")
      (node (ref "D25") (pin "A") (pinfunction "A_A") (pintype "passive"))
      (node (ref "S_P") (pin "1@1") (pinfunction "2_1@1") (pintype "passive"))
      (node (ref "S_P") (pin "1@2") (pinfunction "2_1@2") (pintype "passive"))
    )
    (net (code "56") (name "Net-(D26-PadA)") (class "Default")
      (node (ref "D26") (pin "A") (pinfunction "A_A") (pintype "passive"))
      (node (ref "S_LBRC") (pin "1@1") (pinfunction "2_1@1") (pintype "passive"))
      (node (ref "S_LBRC") (pin "1@2") (pinfunction "2_1@2") (pintype "passive"))
    )
    (net (code "57") (name "Net-(D27-PadA)") (class "Default")
      (node (ref "D27") (pin "A") (pinfunction "A_A") (pintype "passive"))
      (node (ref "S_RBRC") (pin "1@1") (pinfunction "2_1@1") (pintype "passive"))
      (node (ref "S_RBRC") (pin "1@2") (pinfunction "2_1@2") (pintype "passive"))
    )
    (net (code "58") (name "Net-(D28-PadA)") (class "Default")
      (node (ref "D28") (pin "A") (pinfunction "A_A") (pintype "passive"))
      (node (ref "S_BSLS") (pin "1@1") (pinfunction "2_1@1") (pintype "passive"))
      (node (ref "S_BSLS") (pin "1@2") (pinfunction "2_1@2") (pintype "passive"))
      (node (ref "S_BSLS2") (pin "1@1") (pinfunction "2_1@1") (pintype "passive"))
      (node (ref "S_BSLS2") (pin "1@2") (pinfunction "2_1@2") (pintype "passive"))
    )
    (net (code "59") (name "Net-(D30-PadA)") (class "Default")
      (node (ref "D30") (pin "A") (pinfunction "A_A") (pintype "passive"))
      (node (ref "S_A") (pin "1@1") (pinfunction "2_1@1") (pintype "passive"))
      (node (ref "S_A") (pin "1@2") (pinfunction "2_1@2") (pintype "passive"))
    )
    (net (code "60") (name "Net-(D31-PadA)") (class "Default")
      (node (ref "D31") (pin "A") (pinfunction "A_A") (pintype "passive"))
      (node (ref "S_S") (pin "1@1") (pinfunction "2_1@1") (pintype "passive"))
      (node (ref "S_S") (pin "1@2") (pinfunction "2_1@2") (pintype "passive"))
    )
    (net (code "61") (name "Net-(D32-PadA)") (class "Default")
      (node (ref "D32") (pin "A") (pinfunction "A_A") (pintype "passive"))
      (node (ref "S_D") (pin "1@1") (pinfunction "2_1@1") (pintype "passive"))
      (node (ref "S_D") (pin "1@2") (pinfunction "2_1@2") (pintype "passive"))
    )
    (net (code "62") (name "Net-(D33-PadA)") (class "Default")
      (node (ref "D33") (pin "A") (pinfunction "A_A") (pintype "passive"))
      (node (ref "S_F") (pin "1@1") (pinfunction "2_1@1") (pintype "passive"))
      (node (ref "S_F") (pin "1@2") (pinfunction "2_1@2") (pintype "passive"))
    )
    (net (code "63") (name "Net-(D34-PadA)") (class "Default")
      (node (ref "D34") (pin "A") (pinfunction "A_A") (pintype "passive"))
      (node (ref "S_G") (pin "1@1") (pinfunction "2_1@1") (pintype "passive"))
      (node (ref "S_G") (pin "1@2") (pinfunction "2_1@2") (pintype "passive"))
    )
    (net (code "64") (name "Net-(D35-PadA)") (class "Default")
      (node (ref "D35") (pin "A") (pinfunction "A_A") (pintype "passive"))
      (node (ref "S_H") (pin "1@1") (pinfunction "2_1@1") (pintype "passive"))
      (node (ref "S_H") (pin "1@2") (pinfunction "2_1@2") (pintype "passive"))
    )
    (net (code "65") (name "Net-(D36-PadA)") (class "Default")
      (node (ref "D36") (pin "A") (pinfunction "A_A") (pintype "passive"))
      (node (ref "S_J") (pin "1@1") (pinfunction "2_1@1") (pintype "passive"))
      (node (ref "S_J") (pin "1@2") (pinfunction "2_1@2") (pintype "passive"))
    )
    (net (code "66") (name "Net-(D37-PadA)") (class "Default")
      (node (ref "D37") (pin "A") (pinfunction "A_A") (pintype "passive"))
      (node (ref "S_K") (pin "1@1") (pinfunction "2_1@1") (pintype "passive"))
      (node (ref "S_K") (pin "1@2") (pinfunction "2_1@2") (pintype "passive"))
    )
    (net (code "67") (name "Net-(D38-PadA)") (class "Default")
      (node (ref "D38") (pin "A") (pinfunction "A_A") (pintype "passive"))
      (node (ref "S_L") (pin "1@1") (pinfunction "2_1@1") (pintype "passive"))
      (node (ref "S_L") (pin "1@2") (pinfunction "2_1@2") (pintype "passive"))
    )
    (net (code "68") (name "Net-(D39-PadA)") (class "Default")
      (node (ref "D39") (pin "A") (pinfunction "A_A") (pintype "passive"))
      (node (ref "S_SCLN") (pin "1@1") (pinfunction "2_1@1") (pintype "passive"))
      (node (ref "S_SCLN") (pin "1@2") (pinfunction "2_1@2") (pintype "passive"))
    )
    (net (code "69") (name "Net-(D40-PadA)") (class "Default")
      (node (ref "D40") (pin "A") (pinfunction "A_A") (pintype "passive"))
      (node (ref "S_QUOT") (pin "1@1") (pinfunction "2_1@1") (pintype "passive"))
      (node (ref "S_QUOT") (pin "1@2") (pinfunction "2_1@2") (pintype "passive"))
    )
    (net (code "70") (name "Net-(D41-PadA)") (class "Default")
      (node (ref "D41") (pin "A") (pinfunction "A_A") (pintype "passive"))
      (node (ref "S_ENT") (pin "1@1") (pinfunction "2_1@1") (pintype "passive"))
      (node (ref "S_ENT") (pin "1@2") (pinfunction "2_1@2") (pintype "passive"))
      (node (ref "S_ENT2") (pin "1@1") (pinfunction "2_1@1") (pintype "passive"))
      (node (ref "S_ENT2") (pin "1@2") (pinfunction "2_1@2") (pintype "passive"))
    )
    (net (code "71") (name "Net-(D42-PadA)") (class "Default")
      (node (ref "D42") (pin "A") (pinfunction "A_A") (pintype "passive"))
      (node (ref "S_LSFT") (pin "1@1") (pinfunction "2_1@1") (pintype "passive"))
      (node (ref "S_LSFT") (pin "1@2") (pinfunction "2_1@2") (pintype "passive"))
      (node (ref "S_LSFT2") (pin "1@1") (pinfunction "2_1@1") (pintype "passive"))
      (node (ref "S_LSFT2") (pin "1@2") (pinfunction "2_1@2") (pintype "passive"))
    )
    (net (code "72") (name "Net-(D43-PadA)") (class "Default")
      (node (ref "D43") (pin "A") (pinfunction "A_A") (pintype "passive"))
      (node (ref "S_NUBS") (pin "1@1") (pinfunction "2_1@1") (pintype "passive"))
      (node (ref "S_NUBS") (pin "1@2") (pinfunction "2_1@2") (pintype "passive"))
    )
    (net (code "73") (name "Net-(D44-PadA)") (class "Default")
      (node (ref "D44") (pin "A") (pinfunction "A_A") (pintype "passive"))
      (node (ref "S_Z") (pin "1@1") (pinfunction "2_1@1") (pintype "passive"))
      (node (ref "S_Z") (pin "1@2") (pinfunction "2_1@2") (pintype "passive"))
    )
    (net (code "74") (name "Net-(D45-PadA)") (class "Default")
      (node (ref "D45") (pin "A") (pinfunction "A_A") (pintype "passive"))
      (node (ref "S_X") (pin "1@1") (pinfunction "2_1@1") (pintype "passive"))
      (node (ref "S_X") (pin "1@2") (pinfunction "2_1@2") (pintype "passive"))
    )
    (net (code "75") (name "Net-(D46-PadA)") (class "Default")
      (node (ref "D46") (pin "A") (pinfunction "A_A") (pintype "passive"))
      (node (ref "S_C") (pin "1@1") (pinfunction "2_1@1") (pintype "passive"))
      (node (ref "S_C") (pin "1@2") (pinfunction "2_1@2") (pintype "passive"))
    )
    (net (code "76") (name "Net-(D47-PadA)") (class "Default")
      (node (ref "D47") (pin "A") (pinfunction "A_A") (pintype "passive"))
      (node (ref "S_V") (pin "1@1") (pinfunction "2_1@1") (pintype "passive"))
      (node (ref "S_V") (pin "1@2") (pinfunction "2_1@2") (pintype "passive"))
    )
    (net (code "77") (name "Net-(D48-PadA)") (class "Default")
      (node (ref "D48") (pin "A") (pinfunction "A_A") (pintype "passive"))
      (node (ref "S_B") (pin "1@1") (pinfunction "2_1@1") (pintype "passive"))
      (node (ref "S_B") (pin "1@2") (pinfunction "2_1@2") (pintype "passive"))
    )
    (net (code "78") (name "Net-(D49-PadA)") (class "Default")
      (node (ref "D49") (pin "A") (pinfunction "A_A") (pintype "passive"))
      (node (ref "S_N") (pin "1@1") (pinfunction "2_1@1") (pintype "passive"))
      (node (ref "S_N") (pin "1@2") (pinfunction "2_1@2") (pintype "passive"))
    )
    (net (code "79") (name "Net-(D50-PadA)") (class "Default")
      (node (ref "D50") (pin "A") (pinfunction "A_A") (pintype "passive"))
      (node (ref "S_M") (pin "1@1") (pinfunction "2_1@1") (pintype "passive"))
      (node (ref "S_M") (pin "1@2") (pinfunction "2_1@2") (pintype "passive"))
    )
    (net (code "80") (name "Net-(D51-PadA)") (class "Default")
      (node (ref "D51") (pin "A") (pinfunction "A_A") (pintype "passive"))
      (node (ref "S_COM") (pin "1@1") (pinfunction "2_1@1") (pintype "passive"))
      (node (ref "S_COM") (pin "1@2") (pinfunction "2_1@2") (pintype "passive"))
    )
    (net (code "81") (name "Net-(D52-PadA)") (class "Default")
      (node (ref "D52") (pin "A") (pinfunction "A_A") (pintype "passive"))
      (node (ref "S_DOT") (pin "1@1") (pinfunction "2_1@1") (pintype "passive"))
      (node (ref "S_DOT") (pin "1@2") (pinfunction "2_1@2") (pintype "passive"))
    )
    (net (code "82") (name "Net-(D53-PadA)") (class "Default")
      (node (ref "D53") (pin "A") (pinfunction "A_A") (pintype "passive"))
      (node (ref "S_SLSH") (pin "1@1") (pinfunction "2_1@1") (pintype "passive"))
      (node (ref "S_SLSH") (pin "1@2") (pinfunction "2_1@2") (pintype "passive"))
    )
    (net (code "83") (name "Net-(D54-PadA)") (class "Default")
      (node (ref "D54") (pin "A") (pinfunction "A_A") (pintype "passive"))
      (node (ref "S_RSFT") (pin "1@1") (pinfunction "2_1@1") (pintype "passive"))
      (node (ref "S_RSFT") (pin "1@2") (pinfunction "2_1@2") (pintype "passive"))
      (node (ref "S_RSFT2") (pin "1@1") (pinfunction "2_1@1") (pintype "passive"))
      (node (ref "S_RSFT2") (pin "1@2") (pinfunction "2_1@2") (pintype "passive"))
    )
    (net (code "84") (name "Net-(D55-PadA)") (class "Default")
      (node (ref "D55") (pin "A") (pinfunction "A_A") (pintype "passive"))
      (node (ref "S_LCTL") (pin "1@1") (pinfunction "2_1@1") (pintype "passive"))
      (node (ref "S_LCTL") (pin "1@2") (pinfunction "2_1@2") (pintype "passive"))
      (node (ref "S_LCTL_2") (pin "2@1") (pinfunction "1_2@1") (pintype "passive"))
      (node (ref "S_LCTL_2") (pin "2@2") (pinfunction "1_2@2") (pintype "passive"))
    )
    (net (code "85") (name "Net-(D56-PadA)") (class "Default")
      (node (ref "D56") (pin "A") (pinfunction "A_A") (pintype "passive"))
      (node (ref "S_LGUI") (pin "1@1") (pinfunction "2_1@1") (pintype "passive"))
      (node (ref "S_LGUI") (pin "1@2") (pinfunction "2_1@2") (pintype "passive"))
      (node (ref "S_LGUI_2") (pin "2@1") (pinfunction "1_2@1") (pintype "passive"))
      (node (ref "S_LGUI_2") (pin "2@2") (pinfunction "1_2@2") (pintype "passive"))
    )
    (net (code "86") (name "Net-(D57-PadA)") (class "Default")
      (node (ref "D57") (pin "A") (pinfunction "A_A") (pintype "passive"))
      (node (ref "S_LALT") (pin "1@1") (pinfunction "2_1@1") (pintype "passive"))
      (node (ref "S_LALT") (pin "1@2") (pinfunction "2_1@2") (pintype "passive"))
      (node (ref "S_LALT_2") (pin "2@1") (pinfunction "1_2@1") (pintype "passive"))
      (node (ref "S_LALT_2") (pin "2@2") (pinfunction "1_2@2") (pintype "passive"))
    )
    (net (code "87") (name "Net-(D58-PadA)") (class "Default")
      (node (ref "D58") (pin "A") (pinfunction "A_A") (pintype "passive"))
      (node (ref "S_SPC") (pin "1@1") (pinfunction "2_1@1") (pintype "passive"))
      (node (ref "S_SPC") (pin "1@2") (pinfunction "2_1@2") (pintype "passive"))
      (node (ref "S_SPC_2") (pin "2@1") (pinfunction "1_2@1") (pintype "passive"))
      (node (ref "S_SPC_2") (pin "2@2") (pinfunction "1_2@2") (pintype "passive"))
    )
    (net (code "88") (name "Net-(D59-PadA)") (class "Default")
      (node (ref "D59") (pin "A") (pinfunction "A_A") (pintype "passive"))
      (node (ref "S_FN1") (pin "1@1") (pinfunction "2_1@1") (pintype "passive"))
      (node (ref "S_FN1") (pin "1@2") (pinfunction "2_1@2") (pintype "passive"))
    )
    (net (code "89") (name "Net-(D60-PadA)") (class "Default")
      (node (ref "D60") (pin "A") (pinfunction "A_A") (pintype "passive"))
      (node (ref "S_APP") (pin "1@1") (pinfunction "2_1@1") (pintype "passive"))
      (node (ref "S_APP") (pin "1@2") (pinfunction "2_1@2") (pintype "passive"))
      (node (ref "S_RGUI_2") (pin "2@1") (pinfunction "1_2@1") (pintype "passive"))
      (node (ref "S_RGUI_2") (pin "2@2") (pinfunction "1_2@2") (pintype "passive"))
    )
    (net (code "90") (name "Net-(D61-PadA)") (class "Default")
      (node (ref "D61") (pin "A") (pinfunction "A_A") (pintype "passive"))
      (node (ref "S_RALT") (pin "1@1") (pinfunction "2_1@1") (pintype "passive"))
      (node (ref "S_RALT") (pin "1@2") (pinfunction "2_1@2") (pintype "passive"))
      (node (ref "S_RALT_2") (pin "2@1") (pinfunction "1_2@1") (pintype "passive"))
      (node (ref "S_RALT_2") (pin "2@2") (pinfunction "1_2@2") (pintype "passive"))
    )
    (net (code "91") (name "Net-(D62-PadA)") (class "Default")
      (node (ref "D62") (pin "A") (pinfunction "A_A") (pintype "passive"))
      (node (ref "S_RCTL") (pin "1@1") (pinfunction "2_1@1") (pintype "passive"))
      (node (ref "S_RCTL") (pin "1@2") (pinfunction "2_1@2") (pintype "passive"))
      (node (ref "S_RCTL_2") (pin "2@1") (pinfunction "1_2@1") (pintype "passive"))
      (node (ref "S_RCTL_2") (pin "2@2") (pinfunction "1_2@2") (pintype "passive"))
    )
    (net (code "92") (name "Net-(D63-PadA)") (class "Default")
      (node (ref "D63") (pin "A") (pinfunction "A_A") (pintype "passive"))
      (node (ref "S_FN") (pin "1@1") (pinfunction "2_1@1") (pintype "passive"))
      (node (ref "S_FN") (pin "1@2") (pinfunction "2_1@2") (pintype "passive"))
    )
    (net (code "93") (name "Net-(D64-PadA)") (class "Default")
      (node (ref "D64") (pin "A") (pinfunction "A_A") (pintype "passive"))
      (node (ref "S_SPARE") (pin "1@1") (pinfunction "2_1@1") (pintype "passive"))
      (node (ref "S_SPARE") (pin "1@2") (pinfunction "2_1@2") (pintype "passive"))
    )
    (net (code "94") (name "Net-(D65-PadA)") (class "Default")
      (node (ref "D65") (pin "A") (pinfunction "A_A") (pintype "passive"))
      (node (ref "DIP-SW") (pin "1") (pinfunction "1_1") (pintype "passive"))
    )
    (net (code "95") (name "Net-(D66-PadA)") (class "Default")
      (node (ref "D66") (pin "A") (pinfunction "A_A") (pintype "passive"))
      (node (ref "DIP-SW") (pin "2") (pinfunction "2_2") (pintype "passive"))
    )
    (net (code "96") (name "Net-(D67-PadA)") (class "Default")
      (node (ref "D67") (pin "A") (pinfunction "A_A") (pintype "passive"))
      (node (ref "DIP-SW") (pin "3") (pinfunction "3_3") (pintype "passive"))
    )
    (net (code "97") (name "Net-(DIP-SW-Pad4)") (class "Default")
      (node (ref "DIP-SW") (pin "4") (pinfunction "4_4") (pintype "passive"))
      (node (ref "J-VIN") (pin "2") (pinfunction "2_2") (pintype "passive"))
      (node (ref "R3") (pin "2") (pinfunction "2_2") (pintype "passive"))
    )
    (net (code "98") (name "Net-(J-UBS-CC1)") (class "Default")
      (node (ref "J-UBS") (pin "A5") (pinfunction "CC1_A5") (pintype "bidirectional"))
      (node (ref "R1") (pin "1") (pinfunction "1_1") (pintype "passive"))
    )
    (net (code "99") (name "Net-(J-UBS-CC2)") (class "Default")
      (node (ref "J-UBS") (pin "B5") (pinfunction "CC2_B5") (pintype "bidirectional"))
      (node (ref "R2") (pin "1") (pinfunction "1_1") (pintype "passive"))
    )
    (net (code "100") (name "Net-(LED-5-2_DOUT)") (class "Default")
      (node (ref "LED-5") (pin "2-DOUT") (pinfunction "2_DOUT_2-DOUT") (pintype "output"))
      (node (ref "LED-6") (pin "4-DIN") (pinfunction "4_DIN_4-DIN") (pintype "input"))
    )
    (net (code "101") (name "Net-(LED-5-4_DIN)") (class "Default")
      (node (ref "LED-5") (pin "4-DIN") (pinfunction "4_DIN_4-DIN") (pintype "input"))
      (node (ref "LED-CL") (pin "2-DOUT") (pinfunction "2_DOUT_2-DOUT") (pintype "output"))
    )
    (net (code "102") (name "Net-(LED-6-2_DOUT)") (class "Default")
      (node (ref "LED-6") (pin "2-DOUT") (pinfunction "2_DOUT_2-DOUT") (pintype "output"))
      (node (ref "LED-7") (pin "4-DIN") (pinfunction "4_DIN_4-DIN") (pintype "input"))
    )
    (net (code "103") (name "Net-(LED-7-2_DOUT)") (class "Default")
      (node (ref "LED-7") (pin "2-DOUT") (pinfunction "2_DOUT_2-DOUT") (pintype "output"))
      (node (ref "LED-8") (pin "4-DIN") (pinfunction "4_DIN_4-DIN") (pintype "input"))
    )
    (net (code "104") (name "Net-(LED-8-2_DOUT)") (class "Default")
      (node (ref "J-LED") (pin "2") (pinfunction "2_2") (pintype "passive"))
      (node (ref "LED-8") (pin "2-DOUT") (pinfunction "2_DOUT_2-DOUT") (pintype "output"))
    )
    (net (code "105") (name "Net-(LED-CL-4_DIN)") (class "Default")
      (node (ref "LED-CL") (pin "4-DIN") (pinfunction "4_DIN_4-DIN") (pintype "input"))
      (node (ref "R7") (pin "1") (pinfunction "1_1") (pintype "passive"))
    )
    (net (code "106") (name "Net-(S_CAPS2-1)") (class "Default")
      (node (ref "D29") (pin "A") (pinfunction "A_A") (pintype "passive"))
      (node (ref "S_CAPS") (pin "1@1") (pinfunction "2_1@1") (pintype "passive"))
      (node (ref "S_CAPS") (pin "1@2") (pinfunction "2_1@2") (pintype "passive"))
      (node (ref "S_CAPS2") (pin "2") (pinfunction "1_2") (pintype "passive"))
    )
    (net (code "107") (name "Net-(X1-USBHOST_D+)") (class "Default")
      (node (ref "J-HOST") (pin "1") (pinfunction "1_1") (pintype "passive"))
      (node (ref "X1") (pin "35") (pinfunction "USBHOST_D+_35") (pintype "bidirectional"))
    )
    (net (code "108") (name "Net-(X1-USBHOST_D-)") (class "Default")
      (node (ref "J-HOST") (pin "2") (pinfunction "2_2") (pintype "passive"))
      (node (ref "X1") (pin "37") (pinfunction "USBHOST_D-_37") (pintype "bidirectional"))
    )
    (net (code "109") (name "SC1") (class "Default")
      (node (ref "JP-GND") (pin "1") (pinfunction "1_1") (pintype "passive"))
    )
    (net (code "110") (name "SCK") (class "Default")
      (node (ref "M1") (pin "6") (pinfunction "CLK_6") (pintype "bidirectional"))
      (node (ref "R8") (pin "2") (pinfunction "2_2") (pintype "passive"))
      (node (ref "X1") (pin "57") (pinfunction "SPI_SCK_57") (pintype "bidirectional"))
    )
    (net (code "111") (name "VBUS") (class "Default")
      (node (ref "ESD") (pin "P$5") (pinfunction "P$5_P$5") (pintype "bidirectional"))
      (node (ref "J-UBS") (pin "VBUS1") (pinfunction "VBUS_VBUS1") (pintype "bidirectional"))
      (node (ref "J-UBS") (pin "VBUS2") (pinfunction "VBUS_VBUS2") (pintype "bidirectional"))
      (node (ref "PTC") (pin "P$1") (pinfunction "1_P$1") (pintype "passive"))
    )
    (net (code "112") (name "VCC") (class "Default")
      (node (ref "C01") (pin "1") (pinfunction "1_1") (pintype "passive"))
      (node (ref "C02") (pin "1") (pinfunction "1_1") (pintype "passive"))
      (node (ref "C03") (pin "1") (pinfunction "1_1") (pintype "passive"))
      (node (ref "C13") (pin "1") (pinfunction "1_1") (pintype "passive"))
      (node (ref "D00") (pin "A") (pinfunction "A_A") (pintype "passive"))
      (node (ref "J-52") (pin "3") (pinfunction "3_3") (pintype "passive"))
      (node (ref "LM1117") (pin "2") (pinfunction "OUT_2") (pintype "output"))
      (node (ref "M1") (pin "3") (pinfunction "~{WP}_3") (pintype "bidirectional"))
      (node (ref "M1") (pin "7") (pinfunction "~{HLD}_7") (pintype "bidirectional"))
      (node (ref "M1") (pin "8") (pinfunction "VCC_8") (pintype "bidirectional"))
      (node (ref "R9") (pin "2") (pinfunction "2_2") (pintype "passive"))
      (node (ref "X1") (pin "2") (pinfunction "3.3V_2") (pintype "bidirectional"))
      (node (ref "X1") (pin "4") (pinfunction "3.3V_EN_4") (pintype "bidirectional"))
      (node (ref "X1") (pin "74") (pinfunction "3.3V_74") (pintype "bidirectional"))
    )
    (net (code "113") (name "VIN{slash}3") (class "Default")
      (node (ref "R3") (pin "1") (pinfunction "1_1") (pintype "passive"))
      (node (ref "R4") (pin "2") (pinfunction "2_2") (pintype "passive"))
      (node (ref "X1") (pin "49") (pinfunction "BATT_VIN/3_49") (pintype "bidirectional"))
    )
    (net (code "114") (name "VSUP") (class "Default")
      (node (ref "74AH") (pin "6") (pinfunction "5_VCC_6") (pintype "power_in"))
      (node (ref "C04") (pin "1") (pinfunction "1_1") (pintype "passive"))
      (node (ref "C05") (pin "1") (pinfunction "1_1") (pintype "passive"))
      (node (ref "C07") (pin "1") (pinfunction "1_1") (pintype "passive"))
      (node (ref "C08") (pin "1") (pinfunction "1_1") (pintype "passive"))
      (node (ref "C09") (pin "1") (pinfunction "1_1") (pintype "passive"))
      (node (ref "C10") (pin "1") (pinfunction "1_1") (pintype "passive"))
      (node (ref "C11") (pin "1") (pinfunction "1_1") (pintype "passive"))
      (node (ref "C12") (pin "1") (pinfunction "1_1") (pintype "passive"))
      (node (ref "D00") (pin "C") (pinfunction "C_C") (pintype "passive"))
      (node (ref "DIP-SW") (pin "5") (pinfunction "5_5") (pintype "passive"))
      (node (ref "J-LED") (pin "3") (pinfunction "3_3") (pintype "passive"))
      (node (ref "J-UDB") (pin "1") (pinfunction "VCC_1") (pintype "power_in"))
      (node (ref "J-VIN") (pin "1") (pinfunction "1_1") (pintype "passive"))
      (node (ref "LED-5") (pin "1-VDD") (pinfunction "1_VDD_1-VDD") (pintype "power_in"))
      (node (ref "LED-6") (pin "1-VDD") (pinfunction "1_VDD_1-VDD") (pintype "power_in"))
      (node (ref "LED-7") (pin "1-VDD") (pinfunction "1_VDD_1-VDD") (pintype "power_in"))
      (node (ref "LED-8") (pin "1-VDD") (pinfunction "1_VDD_1-VDD") (pintype "power_in"))
      (node (ref "LED-CL") (pin "1-VDD") (pinfunction "1_VDD_1-VDD") (pintype "power_in"))
      (node (ref "LM1117") (pin "3") (pinfunction "IN_3") (pintype "input"))
      (node (ref "PTC") (pin "P$2") (pinfunction "2_P$2") (pintype "passive"))
      (node (ref "TVS") (pin "P$1") (pinfunction "1_P$1") (pintype "passive"))
      (node (ref "X1") (pin "9") (pinfunction "USB_VIN_9") (pintype "bidirectional"))
    )
    (net (code "115") (name "unconnected-(LM1117-OUT-Pad4)") (class "Default")
      (node (ref "LM1117") (pin "4") (pinfunction "OUT_4") (pintype "output"))
    )
    (net (code "116") (name "unconnected-(X1-AUD_MCLK-Pad58)") (class "Default")
      (node (ref "X1") (pin "58") (pinfunction "AUD_MCLK_58") (pintype "bidirectional"))
    )
    (net (code "117") (name "unconnected-(X1-CAN-RX-Pad41)") (class "Default")
      (node (ref "X1") (pin "41") (pinfunction "CAN-RX_41") (pintype "bidirectional"))
    )
    (net (code "118") (name "unconnected-(X1-CAN-TX-Pad43)") (class "Default")
      (node (ref "X1") (pin "43") (pinfunction "CAN-TX_43") (pintype "bidirectional"))
    )
    (net (code "119") (name "unconnected-(X1-CTS1-Pad15)") (class "Default")
      (node (ref "X1") (pin "15") (pinfunction "CTS1_15") (pintype "bidirectional"))
    )
    (net (code "120") (name "unconnected-(X1-G4{slash}BUS4-Pad48)") (class "Default")
      (node (ref "X1") (pin "48") (pinfunction "G4/BUS4_48") (pintype "bidirectional"))
    )
    (net (code "121") (name "unconnected-(X1-G5{slash}BUS5-Pad73)") (class "Default")
      (node (ref "X1") (pin "73") (pinfunction "G5/BUS5_73") (pintype "bidirectional"))
    )
    (net (code "122") (name "unconnected-(X1-G6{slash}BUS6-Pad71)") (class "Default")
      (node (ref "X1") (pin "71") (pinfunction "G6/BUS6_71") (pintype "bidirectional"))
    )
    (net (code "123") (name "unconnected-(X1-G7{slash}BUS7-Pad69)") (class "Default")
      (node (ref "X1") (pin "69") (pinfunction "G7/BUS7_69") (pintype "bidirectional"))
    )
    (net (code "124") (name "unconnected-(X1-G8-Pad67)") (class "Default")
      (node (ref "X1") (pin "67") (pinfunction "G8_67") (pintype "bidirectional"))
    )
    (net (code "125") (name "unconnected-(X1-G9{slash}ADC_D-{slash}CAM_HSYNC-Pad65)") (class "Default")
      (node (ref "X1") (pin "65") (pinfunction "G9/ADC_D-/CAM_HSYNC_65") (pintype "bidirectional"))
    )
    (net (code "126") (name "unconnected-(X1-G11-Pad8)") (class "Default")
      (node (ref "X1") (pin "8") (pinfunction "G11_8") (pintype "bidirectional"))
    )
    (net (code "127") (name "unconnected-(X1-I2C_SCL1-Pad53)") (class "Default")
      (node (ref "X1") (pin "53") (pinfunction "I2C_SCL1_53") (pintype "bidirectional"))
    )
    (net (code "128") (name "unconnected-(X1-I2C_SDA1-Pad51)") (class "Default")
      (node (ref "X1") (pin "51") (pinfunction "I2C_SDA1_51") (pintype "bidirectional"))
    )
    (net (code "129") (name "unconnected-(X1-RTC_3V-Pad72)") (class "Default")
      (node (ref "X1") (pin "72") (pinfunction "RTC_3V_72") (pintype "bidirectional"))
    )
    (net (code "130") (name "unconnected-(X1-RTS1-Pad13)") (class "Default")
      (node (ref "X1") (pin "13") (pinfunction "RTS1_13") (pintype "bidirectional"))
    )
    (net (code "131") (name "unconnected-(X1-RX2-Pad20)") (class "Default")
      (node (ref "X1") (pin "20") (pinfunction "RX2_20") (pintype "bidirectional"))
    )
    (net (code "132") (name "unconnected-(X1-SDIO_DATA1-Pad66)") (class "Default")
      (node (ref "X1") (pin "66") (pinfunction "SDIO_DATA1_66") (pintype "bidirectional"))
    )
    (net (code "133") (name "unconnected-(X1-SDIO_DATA2-Pad68)") (class "Default")
      (node (ref "X1") (pin "68") (pinfunction "SDIO_DATA2_68") (pintype "bidirectional"))
    )
    (net (code "134") (name "unconnected-(X1-SPI_SCK1{slash}SDIO_CLK-Pad60)") (class "Default")
      (node (ref "X1") (pin "60") (pinfunction "SPI_SCK1/SDIO_CLK_60") (pintype "bidirectional"))
    )
    (net (code "135") (name "unconnected-(X1-SPI_SDI1{slash}SDIO_DATA0-Pad64)") (class "Default")
      (node (ref "X1") (pin "64") (pinfunction "SPI_SDI1/SDIO_DATA0_64") (pintype "bidirectional"))
    )
    (net (code "136") (name "unconnected-(X1-SPI_SDO1{slash}SDIO_CMD-Pad62)") (class "Default")
      (node (ref "X1") (pin "62") (pinfunction "SPI_SDO1/SDIO_CMD_62") (pintype "bidirectional"))
    )
    (net (code "137") (name "unconnected-(X1-SPI_~{CS1}{slash}SDIO_DATA3-Pad70)") (class "Default")
      (node (ref "X1") (pin "70") (pinfunction "SPI_~{CS1}/SDIO_DATA3_70") (pintype "bidirectional"))
    )
    (net (code "138") (name "unconnected-(X1-SWDCK-Pad21)") (class "Default")
      (node (ref "X1") (pin "21") (pinfunction "SWDCK_21") (pintype "bidirectional"))
    )
    (net (code "139") (name "unconnected-(X1-SWDIO-Pad23)") (class "Default")
      (node (ref "X1") (pin "23") (pinfunction "SWDIO_23") (pintype "bidirectional"))
    )
    (net (code "140") (name "unconnected-(X1-TX2-Pad22)") (class "Default")
      (node (ref "X1") (pin "22") (pinfunction "TX2_22") (pintype "bidirectional"))
    )
    (net (code "141") (name "~{BOOT}") (class "Default")
      (node (ref "C14") (pin "1") (pinfunction "1_1") (pintype "passive"))
      (node (ref "D80") (pin "1") (pinfunction "A1_1") (pintype "passive"))
      (node (ref "S2") (pin "2") (pinfunction "3_2") (pintype "passive"))
      (node (ref "X1") (pin "11") (pinfunction "~{BOOT}_11") (pintype "bidirectional"))
    )
    (net (code "142") (name "~{RESET}") (class "Default")
      (node (ref "D80") (pin "2") (pinfunction "A2_2") (pintype "passive"))
      (node (ref "S1") (pin "2") (pinfunction "3_2") (pintype "passive"))
      (node (ref "X1") (pin "6") (pinfunction "~{RESET}_6") (pintype "bidirectional"))
    )
  )
)
